# BBB_ADC7_inputs_with_mux_Ver1_Rev1.net
KiCad netlist of a schematic drawn in Altium Designer
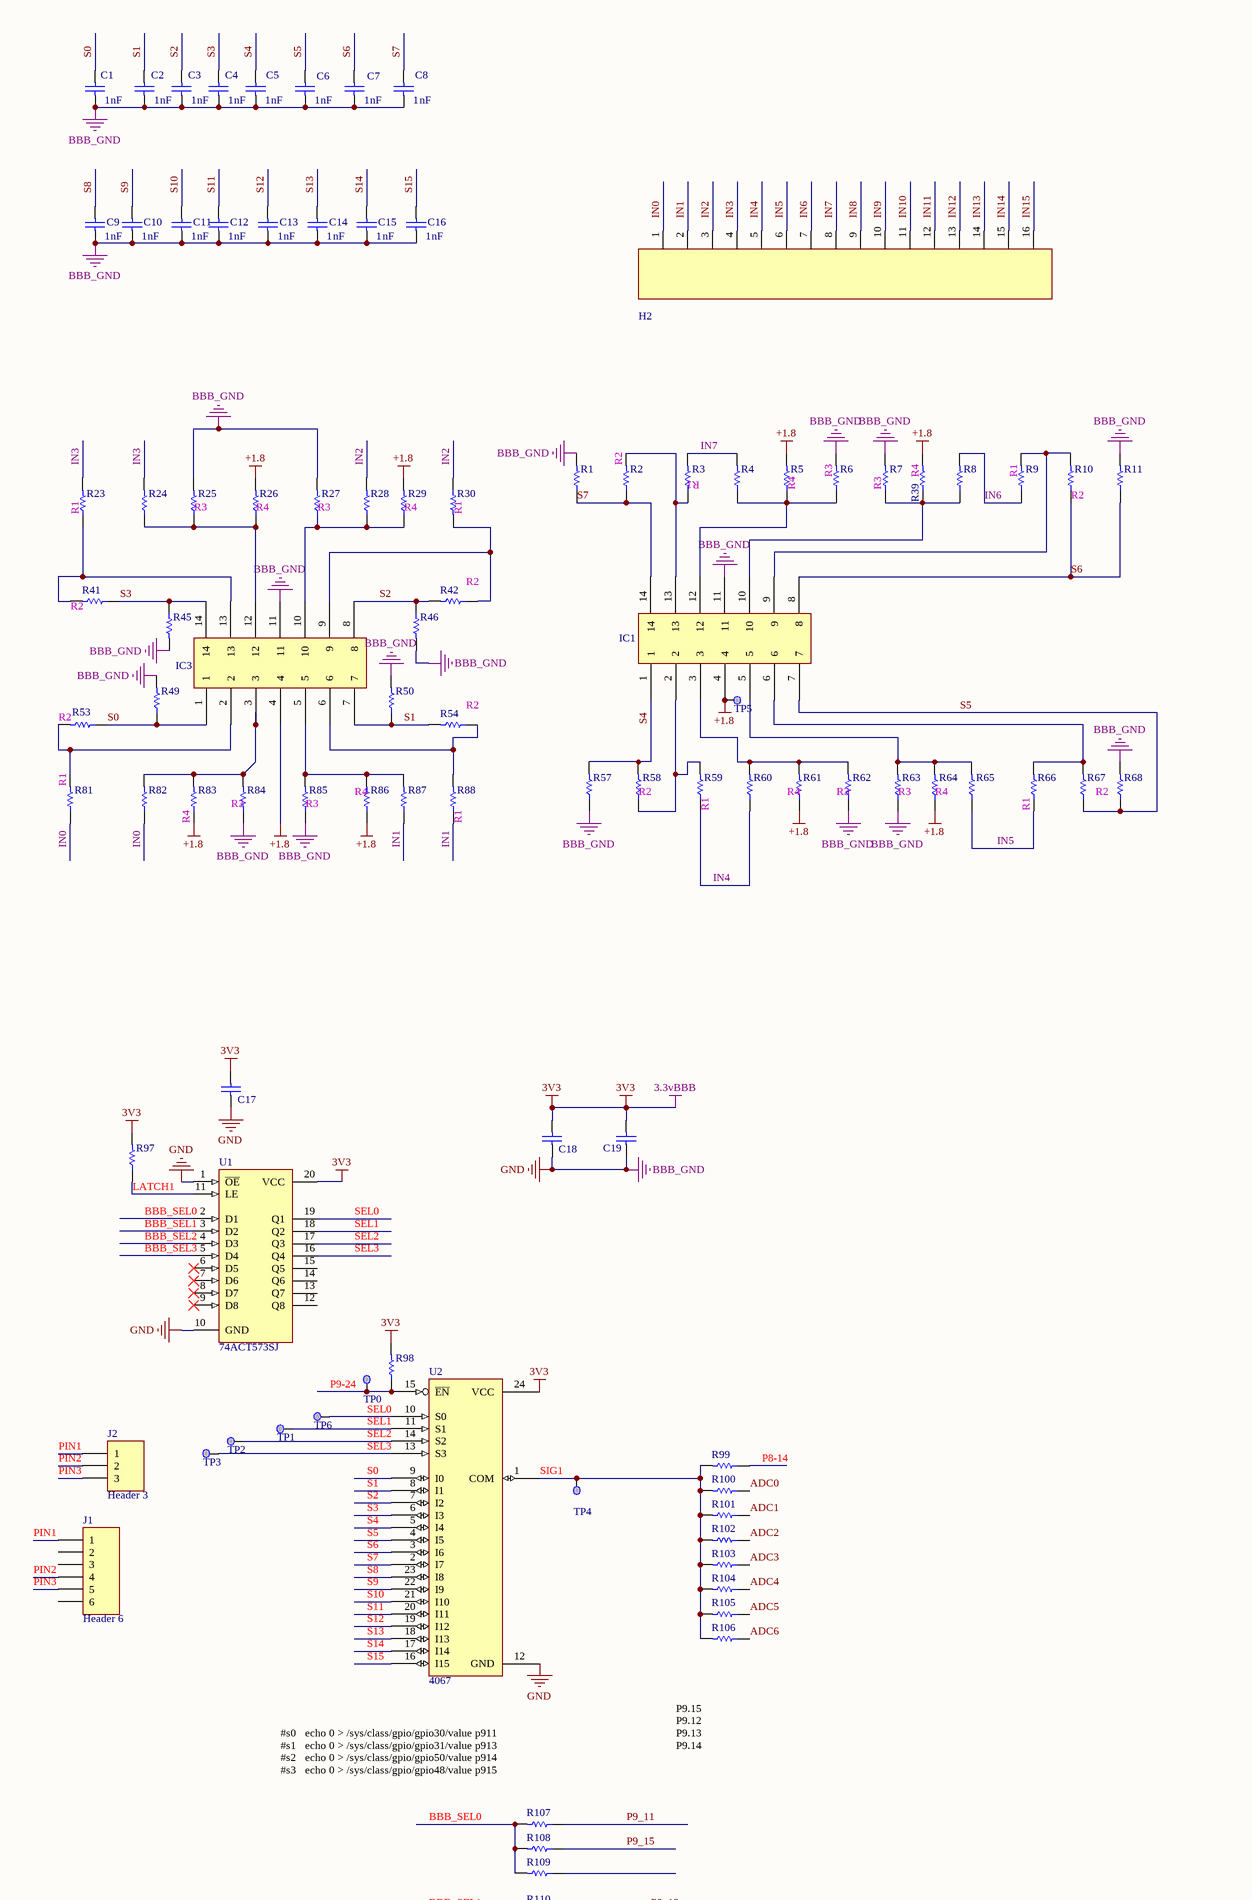
[diagram p0: BBB_ADC7_inputs_with_mux_Ver1 Rev1.SchDoc, top left]
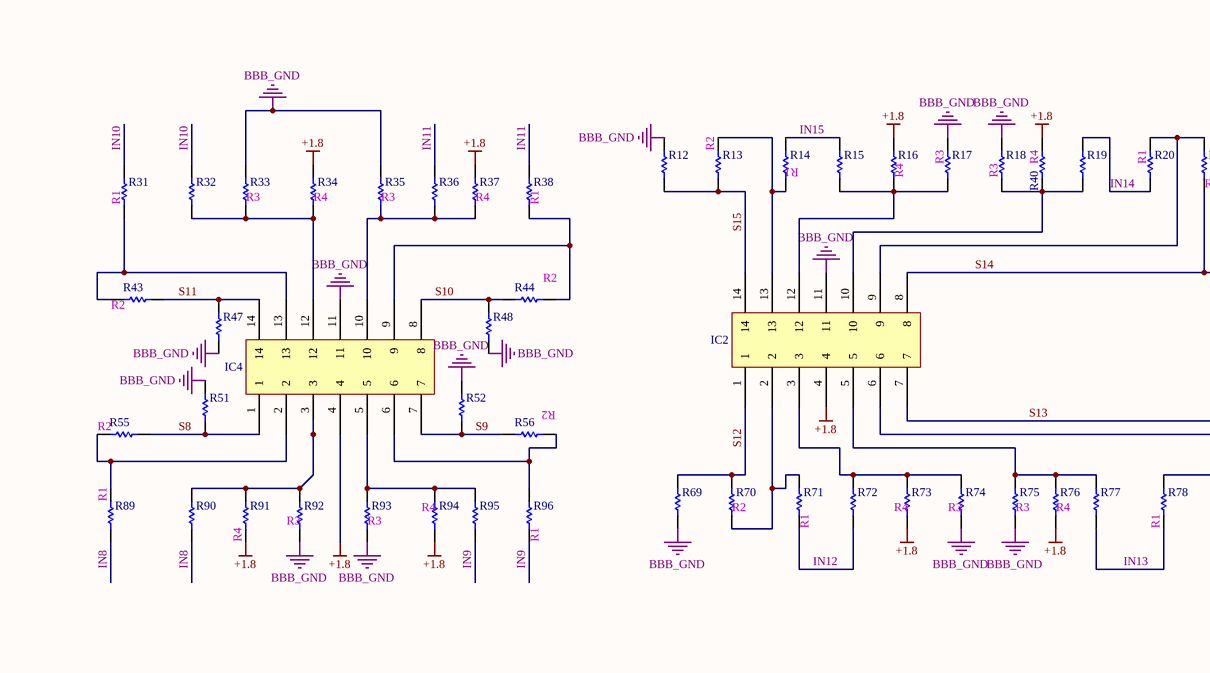
[diagram p1: BBB_ADC7_inputs_with_mux_Ver1 Rev1.SchDoc, top middle]
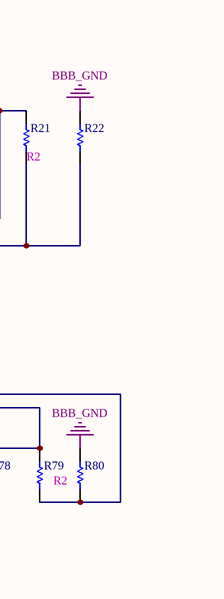
[diagram p2: BBB_ADC7_inputs_with_mux_Ver1 Rev1.SchDoc, top right]
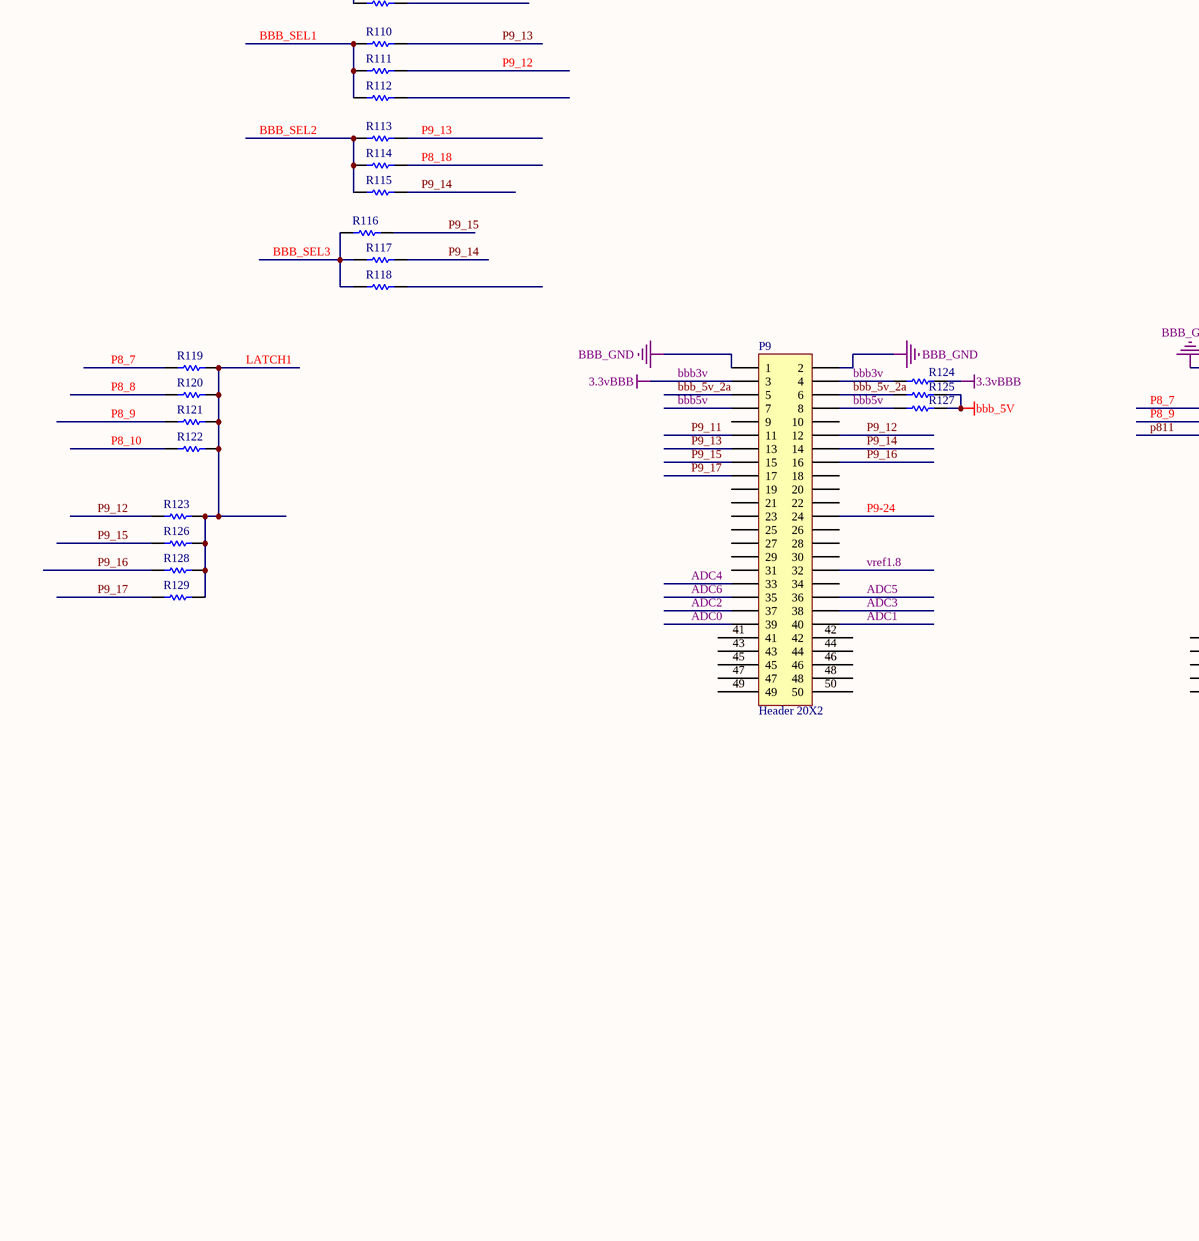
[diagram p3: BBB_ADC7_inputs_with_mux_Ver1 Rev1.SchDoc, bottom left]
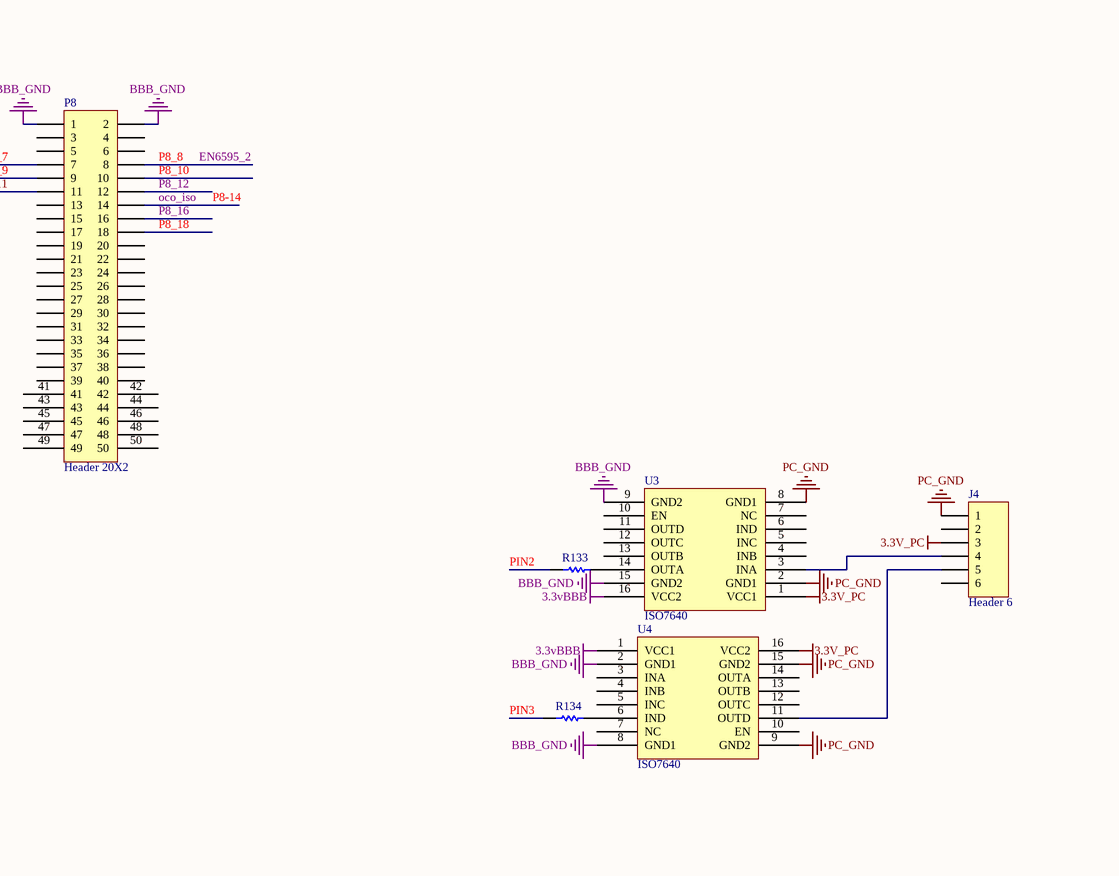
[diagram p4: BBB_ADC7_inputs_with_mux_Ver1 Rev1.SchDoc, bottom middle]
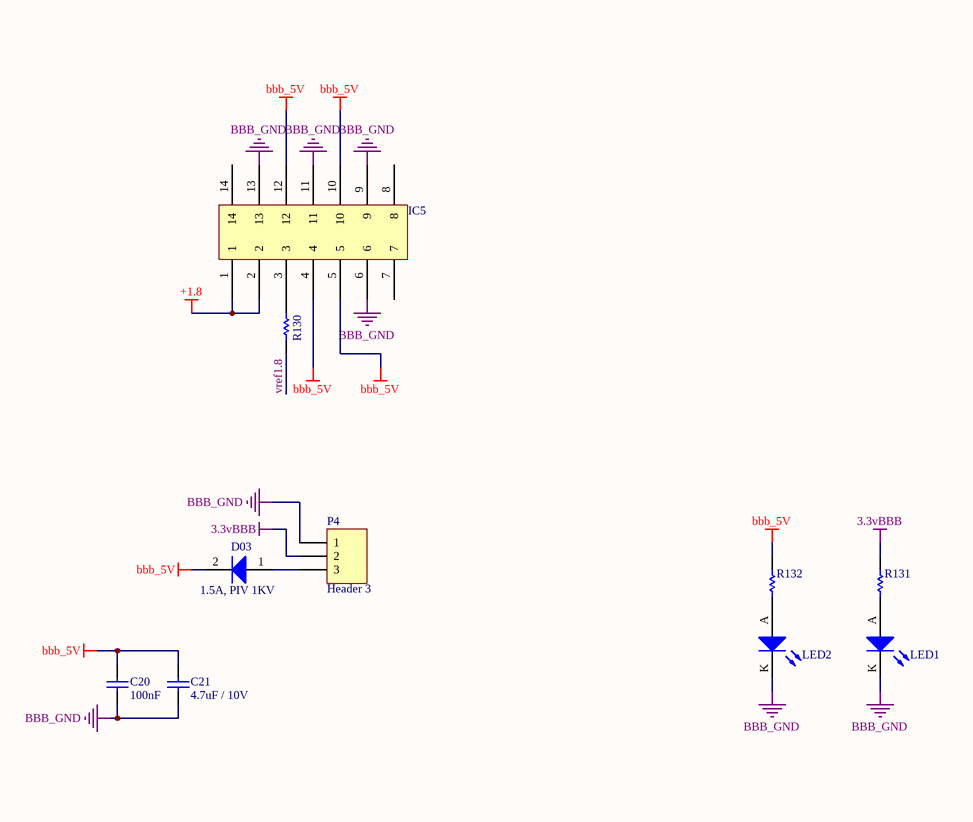
[diagram p5: BBB_ADC7_inputs_with_mux_Ver1 Rev1.SchDoc, bottom right]

(export (version "E")
  (design (tool "Eeschema 10.0.6"))
  (components
    (comp (ref "C1")
      (value "CAPACITOR NONPOLAR SMT")
      (footprint "C0402")
      (description "Capacitor ceramic, SMD 0402, 1 nF, +/-10%, 50 V dc")
      (fields
        (field (name "SMLPARTNO") "BCS22A-102")
        (field (name "UNITS OF CAPACITANCE") "nF")
        (field (name "CAPACITANCE") "1")
        (field (name "PUBLISHER") "Altium Limited")
      )
      (libsource (lib "Altium_DB-Lib_Agile9.3") (part "CAPACITOR NONPOLAR SMT"))
    )
    (comp (ref "C2")
      (value "CAPACITOR NONPOLAR SMT")
      (footprint "C0402")
      (description "Capacitor ceramic, SMD 0402, 1 nF, +/-10%, 50 V dc")
      (fields
        (field (name "SMLPARTNO") "BCS22A-102")
        (field (name "UNITS OF CAPACITANCE") "nF")
        (field (name "CAPACITANCE") "1")
        (field (name "PUBLISHER") "Altium Limited")
      )
      (libsource (lib "Altium_DB-Lib_Agile9.3") (part "CAPACITOR NONPOLAR SMT"))
    )
    (comp (ref "C3")
      (value "CAPACITOR NONPOLAR SMT")
      (footprint "C0402")
      (description "Capacitor ceramic, SMD 0402, 1 nF, +/-10%, 50 V dc")
      (fields
        (field (name "SMLPARTNO") "BCS22A-102")
        (field (name "UNITS OF CAPACITANCE") "nF")
        (field (name "CAPACITANCE") "1")
        (field (name "PUBLISHER") "Altium Limited")
      )
      (libsource (lib "Altium_DB-Lib_Agile9.3") (part "CAPACITOR NONPOLAR SMT"))
    )
    (comp (ref "C4")
      (value "CAPACITOR NONPOLAR SMT")
      (footprint "C0402")
      (description "Capacitor ceramic, SMD 0402, 1 nF, +/-10%, 50 V dc")
      (fields
        (field (name "SMLPARTNO") "BCS22A-102")
        (field (name "UNITS OF CAPACITANCE") "nF")
        (field (name "CAPACITANCE") "1")
        (field (name "PUBLISHER") "Altium Limited")
      )
      (libsource (lib "Altium_DB-Lib_Agile9.3") (part "CAPACITOR NONPOLAR SMT"))
    )
    (comp (ref "C5")
      (value "CAPACITOR NONPOLAR SMT")
      (footprint "C0402")
      (description "Capacitor ceramic, SMD 0402, 1 nF, +/-10%, 50 V dc")
      (fields
        (field (name "SMLPARTNO") "BCS22A-102")
        (field (name "UNITS OF CAPACITANCE") "nF")
        (field (name "CAPACITANCE") "1")
        (field (name "PUBLISHER") "Altium Limited")
      )
      (libsource (lib "Altium_DB-Lib_Agile9.3") (part "CAPACITOR NONPOLAR SMT"))
    )
    (comp (ref "C6")
      (value "CAPACITOR NONPOLAR SMT")
      (footprint "C0402")
      (description "Capacitor ceramic, SMD 0402, 1 nF, +/-10%, 50 V dc")
      (fields
        (field (name "SMLPARTNO") "BCS22A-102")
        (field (name "UNITS OF CAPACITANCE") "nF")
        (field (name "CAPACITANCE") "1")
        (field (name "PUBLISHER") "Altium Limited")
      )
      (libsource (lib "Altium_DB-Lib_Agile9.3") (part "CAPACITOR NONPOLAR SMT"))
    )
    (comp (ref "C7")
      (value "CAPACITOR NONPOLAR SMT")
      (footprint "C0402")
      (description "Capacitor ceramic, SMD 0402, 1 nF, +/-10%, 50 V dc")
      (fields
        (field (name "SMLPARTNO") "BCS22A-102")
        (field (name "UNITS OF CAPACITANCE") "nF")
        (field (name "CAPACITANCE") "1")
        (field (name "PUBLISHER") "Altium Limited")
      )
      (libsource (lib "Altium_DB-Lib_Agile9.3") (part "CAPACITOR NONPOLAR SMT"))
    )
    (comp (ref "C8")
      (value "CAPACITOR NONPOLAR SMT")
      (footprint "C0402")
      (description "Capacitor ceramic, SMD 0402, 1 nF, +/-10%, 50 V dc")
      (fields
        (field (name "SMLPARTNO") "BCS22A-102")
        (field (name "UNITS OF CAPACITANCE") "nF")
        (field (name "CAPACITANCE") "1")
        (field (name "PUBLISHER") "Altium Limited")
      )
      (libsource (lib "Altium_DB-Lib_Agile9.3") (part "CAPACITOR NONPOLAR SMT"))
    )
    (comp (ref "C9")
      (value "CAPACITOR NONPOLAR SMT")
      (footprint "C0402")
      (description "Capacitor ceramic, SMD 0402, 1 nF, +/-10%, 50 V dc")
      (fields
        (field (name "SMLPARTNO") "BCS22A-102")
        (field (name "UNITS OF CAPACITANCE") "nF")
        (field (name "CAPACITANCE") "1")
        (field (name "PUBLISHER") "Altium Limited")
      )
      (libsource (lib "Altium_DB-Lib_Agile9.3") (part "CAPACITOR NONPOLAR SMT"))
    )
    (comp (ref "C10")
      (value "CAPACITOR NONPOLAR SMT")
      (footprint "C0402")
      (description "Capacitor ceramic, SMD 0402, 1 nF, +/-10%, 50 V dc")
      (fields
        (field (name "SMLPARTNO") "BCS22A-102")
        (field (name "UNITS OF CAPACITANCE") "nF")
        (field (name "CAPACITANCE") "1")
        (field (name "PUBLISHER") "Altium Limited")
      )
      (libsource (lib "Altium_DB-Lib_Agile9.3") (part "CAPACITOR NONPOLAR SMT"))
    )
    (comp (ref "C11")
      (value "CAPACITOR NONPOLAR SMT")
      (footprint "C0402")
      (description "Capacitor ceramic, SMD 0402, 1 nF, +/-10%, 50 V dc")
      (fields
        (field (name "SMLPARTNO") "BCS22A-102")
        (field (name "UNITS OF CAPACITANCE") "nF")
        (field (name "CAPACITANCE") "1")
        (field (name "PUBLISHER") "Altium Limited")
      )
      (libsource (lib "Altium_DB-Lib_Agile9.3") (part "CAPACITOR NONPOLAR SMT"))
    )
    (comp (ref "C12")
      (value "CAPACITOR NONPOLAR SMT")
      (footprint "C0402")
      (description "Capacitor ceramic, SMD 0402, 1 nF, +/-10%, 50 V dc")
      (fields
        (field (name "SMLPARTNO") "BCS22A-102")
        (field (name "UNITS OF CAPACITANCE") "nF")
        (field (name "CAPACITANCE") "1")
        (field (name "PUBLISHER") "Altium Limited")
      )
      (libsource (lib "Altium_DB-Lib_Agile9.3") (part "CAPACITOR NONPOLAR SMT"))
    )
    (comp (ref "C13")
      (value "CAPACITOR NONPOLAR SMT")
      (footprint "C0402")
      (description "Capacitor ceramic, SMD 0402, 1 nF, +/-10%, 50 V dc")
      (fields
        (field (name "SMLPARTNO") "BCS22A-102")
        (field (name "UNITS OF CAPACITANCE") "nF")
        (field (name "CAPACITANCE") "1")
        (field (name "PUBLISHER") "Altium Limited")
      )
      (libsource (lib "Altium_DB-Lib_Agile9.3") (part "CAPACITOR NONPOLAR SMT"))
    )
    (comp (ref "C14")
      (value "CAPACITOR NONPOLAR SMT")
      (footprint "C0402")
      (description "Capacitor ceramic, SMD 0402, 1 nF, +/-10%, 50 V dc")
      (fields
        (field (name "SMLPARTNO") "BCS22A-102")
        (field (name "UNITS OF CAPACITANCE") "nF")
        (field (name "CAPACITANCE") "1")
        (field (name "PUBLISHER") "Altium Limited")
      )
      (libsource (lib "Altium_DB-Lib_Agile9.3") (part "CAPACITOR NONPOLAR SMT"))
    )
    (comp (ref "C15")
      (value "CAPACITOR NONPOLAR SMT")
      (footprint "C0402")
      (description "Capacitor ceramic, SMD 0402, 1 nF, +/-10%, 50 V dc")
      (fields
        (field (name "SMLPARTNO") "BCS22A-102")
        (field (name "UNITS OF CAPACITANCE") "nF")
        (field (name "CAPACITANCE") "1")
        (field (name "PUBLISHER") "Altium Limited")
      )
      (libsource (lib "Altium_DB-Lib_Agile9.3") (part "CAPACITOR NONPOLAR SMT"))
    )
    (comp (ref "C16")
      (value "CAPACITOR NONPOLAR SMT")
      (footprint "C0402")
      (description "Capacitor ceramic, SMD 0402, 1 nF, +/-10%, 50 V dc")
      (fields
        (field (name "SMLPARTNO") "BCS22A-102")
        (field (name "UNITS OF CAPACITANCE") "nF")
        (field (name "CAPACITANCE") "1")
        (field (name "PUBLISHER") "Altium Limited")
      )
      (libsource (lib "Altium_DB-Lib_Agile9.3") (part "CAPACITOR NONPOLAR SMT"))
    )
    (comp (ref "C17")
      (value "4.7uF, 10V")
      (footprint "C0603")
      (description "Capacitor ceramic, SMD 0603, 4.7 uF, +/-10%, 10 V dc")
      (fields (field (name "SMLPARTNO") "BCS129-475") (field (name "PUBLISHER") "Altium Limited"))
      (libsource (lib "Altium_DB-Lib_Agile9.3") (part "CAPACITOR NONPOLAR SMT"))
    )
    (comp (ref "C18")
      (value "4.7uF, 10V")
      (footprint "C0603")
      (description "Capacitor ceramic, SMD 0603, 4.7 uF, +/-10%, 10 V dc")
      (fields (field (name "SMLPARTNO") "BCS129-475") (field (name "PUBLISHER") "Altium Limited"))
      (libsource (lib "Altium_DB-Lib_Agile9.3") (part "CAPACITOR NONPOLAR SMT"))
    )
    (comp (ref "C19")
      (value "4.7uF, 10V")
      (footprint "C0603")
      (description "Capacitor ceramic, SMD 0603, 4.7 uF, +/-10%, 10 V dc")
      (fields (field (name "SMLPARTNO") "BCS129-475") (field (name "PUBLISHER") "Altium Limited"))
      (libsource (lib "Altium_DB-Lib_Agile9.3") (part "CAPACITOR NONPOLAR SMT"))
    )
    (comp (ref "C20")
      (value "100nF")
      (footprint "C0603")
      (description "Capacitor ceramic, SMD 0603, 100 nF, +/-10%, 16 V dc")
      (fields (field (name "SMLPARTNO") "BCS129-104") (field (name "PUBLISHER") "Altium Limited"))
      (libsource (lib "Altium_DB-Lib_Agile9.3") (part "CAPACITOR NONPOLAR SMT"))
    )
    (comp (ref "C21")
      (value "4.7uF / 10V")
      (footprint "C0603")
      (description "Capacitor ceramic, SMD 0603, 4.7 uF, +/-10%, 10 V dc")
      (fields (field (name "SMLPARTNO") "BCS129-475") (field (name "PUBLISHER") "Altium Limited"))
      (libsource (lib "Altium_DB-Lib_Agile9.3") (part "CAPACITOR NONPOLAR SMT"))
    )
    (comp (ref "D03")
      (value "1.5A, PIV 1KV")
      (footprint "DIODE_DO-214AA(SMB)")
      (description "Diode high voltage, SMD DO-214AA, If 1.5 A, PIV 1 kV")
      (fields (field (name "SMLPARTNO") "BDS334-001") (field (name "PUBLISHER") "Altium Limited"))
      (libsource (lib "Altium_DB-Lib_Agile9.3") (part "DIODE"))
    )
    (comp (ref "H2")
      (value "connector 16 pin male_ stright")
      (footprint "16 pin male stright")
      (libsource (lib "PPE_integrated_LIB") (part "connector 16 pin male_ stright"))
    )
    (comp (ref "IC1")
      (value "OPamp")
      (footprint "SOIC-14")
      (fields (field (name "SMLPARTNO") "BIS114-020"))
      (libsource (lib "Schlib2") (part "OPamp"))
    )
    (comp (ref "IC2")
      (value "OPamp")
      (footprint "SOIC-14")
      (fields (field (name "SMLPARTNO") "BIS114-020"))
      (libsource (lib "Schlib2") (part "OPamp"))
    )
    (comp (ref "IC3")
      (value "OPamp")
      (footprint "SOIC-14")
      (fields (field (name "SMLPARTNO") "BIS114-020"))
      (libsource (lib "Schlib2") (part "OPamp"))
    )
    (comp (ref "IC4")
      (value "OPamp")
      (footprint "SOIC-14")
      (fields (field (name "SMLPARTNO") "BIS114-020"))
      (libsource (lib "Schlib2") (part "OPamp"))
    )
    (comp (ref "IC5")
      (value "OPamp")
      (footprint "SOIC-14")
      (fields (field (name "SMLPPARTNO") "BIS114-020"))
      (libsource (lib "Schlib2") (part "OPamp"))
    )
    (comp (ref "J1")
      (value "Header 6")
      (footprint "HDR1X6")
      (description "Header, 6-Pin")
      (fields (field (name "PUBLISHER") "Altium Limited"))
      (libsource (lib "Miscellaneous Connectors") (part "Header 6"))
    )
    (comp (ref "J2")
      (value "Header 3")
      (footprint "HDR1X3")
      (description "Header, 3-Pin")
      (fields (field (name "PUBLISHER") "Altium Limited"))
      (libsource (lib "Miscellaneous Connectors") (part "Header 3"))
    )
    (comp (ref "J4")
      (value "Header 6")
      (footprint "HDR1X6")
      (description "Header, 6-Pin")
      (fields (field (name "PUBLISHER") "Altium Limited"))
      (libsource (lib "Miscellaneous Connectors") (part "Header 6"))
    )
    (comp (ref "LED1")
      (value "LED")
      (footprint "0537, LED, 1206")
      (description "Optoelectronic LED, SMD 1206, red colour")
      (fields (field (name "SMLPARTNO") "BDS461-001") (field (name "PUBLISHER") "Altium Limited"))
      (libsource (lib "Altium_DB-Lib_Agile9.3") (part "LED"))
    )
    (comp (ref "LED2")
      (value "LED")
      (footprint "0537, LED, 1206")
      (description "Optoelectronic LED, SMD 1206, red colour")
      (fields (field (name "SMLPARTNO") "BDS461-001") (field (name "PUBLISHER") "Altium Limited"))
      (libsource (lib "Altium_DB-Lib_Agile9.3") (part "LED"))
    )
    (comp (ref "P4")
      (value "Header 3")
      (footprint "HDR1X3")
      (description "Header, 3-Pin")
      (fields (field (name "PUBLISHER") "Altium Limited"))
      (libsource (lib "BBB ADS1247") (part "Header 3"))
    )
    (comp (ref "P8")
      (value "Header 20X2")
      (footprint "BBBHEADERNOHOLE")
      (description "Header, 20-Pin, Dual row")
      (fields (field (name "PUBLISHER") "Altium Limited"))
      (libsource (lib "PantherTester") (part "Header 20X2"))
    )
    (comp (ref "P9")
      (value "Header 20X2")
      (footprint "BBBHEADERNOHOLE")
      (description "Header, 20-Pin, Dual row")
      (fields (field (name "PUBLISHER") "Altium Limited"))
      (libsource (lib "PantherTester") (part "Header 20X2"))
    )
    (comp (ref "R1")
      (value "Resistor SMD 0603, 100 k Ohm, +/-5%, 1/10W")
      (footprint "0603")
      (fields (field (name "SMLPARTNO") "BRS131-104") (field (name "TOLERANCE") "+/-5%"))
      (libsource (lib "Altium_DB-Lib_Agile9.3") (part "RESISTOR SMT"))
    )
    (comp (ref "R2")
      (value "Resistor SMD 0603, 1.5 k Ohm, +/-5%, 1/10W")
      (footprint "0603")
      (fields (field (name "SMLPARTNO") "BRS131-152") (field (name "TOLERANCE") "+/-5%"))
      (libsource (lib "Altium_DB-Lib_Agile9.3") (part "RESISTOR SMT"))
    )
    (comp (ref "R3")
      (value "Resistor SMD 0603, 9.1 k Ohm, +/-5%, 1/10W")
      (footprint "0603")
      (fields (field (name "SMLPARTNO") "BRS131-912") (field (name "TOLERANCE") "+/-5%"))
      (libsource (lib "Altium_DB-Lib_Agile9.3") (part "RESISTOR SMT"))
    )
    (comp (ref "R4")
      (value "open")
      (footprint "0603")
      (fields (field (name "TOLERANCE") "+/-5%"))
      (libsource (lib "Altium_DB-Lib_Agile9.3") (part "RESISTOR SMT"))
    )
    (comp (ref "R5")
      (value "Resistor SMD 0603, 6.8 k Ohm, +/-1%, 1/10W")
      (footprint "0603")
      (fields (field (name "SMLPARTNO") "BRS131-682") (field (name "TOLERANCE") "+/-5%"))
      (libsource (lib "Altium_DB-Lib_Agile9.3") (part "RESISTOR SMT"))
    )
    (comp (ref "R6")
      (value "Resistor SMD 0603, 4.7 k Ohm, +/-5%, 1/10W")
      (footprint "0603")
      (fields (field (name "SMLPARTNO") "BRS133-472") (field (name "TOLERANCE") "+/-5%"))
      (libsource (lib "Altium_DB-Lib_Agile9.3") (part "RESISTOR SMT"))
    )
    (comp (ref "R7")
      (value "Resistor SMD 0603, 4.7 k Ohm, +/-5%, 1/10W")
      (footprint "0603")
      (fields (field (name "SMLPARTNO") "BRS133-472") (field (name "TOLERANCE") "+/-5%"))
      (libsource (lib "Altium_DB-Lib_Agile9.3") (part "RESISTOR SMT"))
    )
    (comp (ref "R8")
      (value "open")
      (footprint "0603")
      (fields (field (name "TOLERANCE") "+/-5%"))
      (libsource (lib "Altium_DB-Lib_Agile9.3") (part "RESISTOR SMT"))
    )
    (comp (ref "R9")
      (value "Resistor SMD 0603, 9.1 k Ohm, +/-5%, 1/10W")
      (footprint "0603")
      (fields (field (name "SMLPARTNO") "BRS131-912") (field (name "TOLERANCE") "+/-5%"))
      (libsource (lib "Altium_DB-Lib_Agile9.3") (part "RESISTOR SMT"))
    )
    (comp (ref "R10")
      (value "Resistor SMD 0603, 1.5 k Ohm, +/-5%, 1/10W")
      (footprint "0603")
      (fields (field (name "SMLPARTNO") "BRS131-152") (field (name "TOLERANCE") "+/-5%"))
      (libsource (lib "Altium_DB-Lib_Agile9.3") (part "RESISTOR SMT"))
    )
    (comp (ref "R11")
      (value "Resistor SMD 0603, 100 k Ohm, +/-5%, 1/10W")
      (footprint "0603")
      (fields (field (name "SMLPARTNO") "BRS131-104") (field (name "TOLERANCE") "+/-5%"))
      (libsource (lib "Altium_DB-Lib_Agile9.3") (part "RESISTOR SMT"))
    )
    (comp (ref "R12")
      (value "Resistor SMD 0603, 100 k Ohm, +/-5%, 1/10W")
      (footprint "0603")
      (fields (field (name "SMLPARTNO") "BRS131-104") (field (name "TOLERANCE") "+/-5%"))
      (libsource (lib "Altium_DB-Lib_Agile9.3") (part "RESISTOR SMT"))
    )
    (comp (ref "R13")
      (value "Resistor SMD 0603, 1.5 k Ohm, +/-5%, 1/10W")
      (footprint "0603")
      (fields (field (name "SMLPARTNO") "BRS131-152") (field (name "TOLERANCE") "+/-5%"))
      (libsource (lib "Altium_DB-Lib_Agile9.3") (part "RESISTOR SMT"))
    )
    (comp (ref "R14")
      (value "Resistor SMD 0603, 9.1 k Ohm, +/-5%, 1/10W")
      (footprint "0603")
      (fields (field (name "SMLPARTNO") "BRS131-912") (field (name "TOLERANCE") "+/-5%"))
      (libsource (lib "Altium_DB-Lib_Agile9.3") (part "RESISTOR SMT"))
    )
    (comp (ref "R15")
      (value "open")
      (footprint "0603")
      (fields (field (name "TOLERANCE") "+/-5%"))
      (libsource (lib "Altium_DB-Lib_Agile9.3") (part "RESISTOR SMT"))
    )
    (comp (ref "R16")
      (value "Resistor SMD 0603, 6.8 k Ohm, +/-1%, 1/10W")
      (footprint "0603")
      (fields (field (name "SMLPARTNO") "BRS131-682") (field (name "TOLERANCE") "+/-5%"))
      (libsource (lib "Altium_DB-Lib_Agile9.3") (part "RESISTOR SMT"))
    )
    (comp (ref "R17")
      (value "Resistor SMD 0603, 4.7 k Ohm, +/-5%, 1/10W")
      (footprint "0603")
      (fields (field (name "SMLPARTNO") "BRS133-472") (field (name "TOLERANCE") "+/-5%"))
      (libsource (lib "Altium_DB-Lib_Agile9.3") (part "RESISTOR SMT"))
    )
    (comp (ref "R18")
      (value "Resistor SMD 0603, 4.7 k Ohm, +/-5%, 1/10W")
      (footprint "0603")
      (fields (field (name "SMLPARTNO") "BRS133-472") (field (name "TOLERANCE") "+/-5%"))
      (libsource (lib "Altium_DB-Lib_Agile9.3") (part "RESISTOR SMT"))
    )
    (comp (ref "R19")
      (value "open")
      (footprint "0603")
      (fields (field (name "TOLERANCE") "+/-5%"))
      (libsource (lib "Altium_DB-Lib_Agile9.3") (part "RESISTOR SMT"))
    )
    (comp (ref "R20")
      (value "Resistor SMD 0603, 9.1 k Ohm, +/-5%, 1/10W")
      (footprint "0603")
      (fields (field (name "SMLPARTNO") "BRS131-912") (field (name "TOLERANCE") "+/-5%"))
      (libsource (lib "Altium_DB-Lib_Agile9.3") (part "RESISTOR SMT"))
    )
    (comp (ref "R21")
      (value "Resistor SMD 0603, 1.5 k Ohm, +/-5%, 1/10W")
      (footprint "0603")
      (fields (field (name "SMLPARTNO") "BRS131-152") (field (name "TOLERANCE") "+/-5%"))
      (libsource (lib "Altium_DB-Lib_Agile9.3") (part "RESISTOR SMT"))
    )
    (comp (ref "R22")
      (value "Resistor SMD 0603, 100 k Ohm, +/-5%, 1/10W")
      (footprint "0603")
      (fields (field (name "SMLPARTNO") "BRS131-104") (field (name "TOLERANCE") "+/-5%"))
      (libsource (lib "Altium_DB-Lib_Agile9.3") (part "RESISTOR SMT"))
    )
    (comp (ref "R23")
      (value "Resistor SMD 0603, 9.1 k Ohm, +/-5%, 1/10W")
      (footprint "0603")
      (fields (field (name "SMLPARTNO") "BRS131-912") (field (name "TOLERANCE") "+/-5%"))
      (libsource (lib "Altium_DB-Lib_Agile9.3") (part "RESISTOR SMT"))
    )
    (comp (ref "R24")
      (value "OPEN")
      (footprint "0603")
      (fields (field (name "TOLERANCE") "+/-5%"))
      (libsource (lib "Altium_DB-Lib_Agile9.3") (part "RESISTOR SMT"))
    )
    (comp (ref "R25")
      (value "Resistor SMD 0603, 4.7 k Ohm, +/-5%, 1/10W")
      (footprint "0603")
      (fields (field (name "SMLPARTNO") "BRS133-472") (field (name "TOLERANCE") "+/-5%"))
      (libsource (lib "Altium_DB-Lib_Agile9.3") (part "RESISTOR SMT"))
    )
    (comp (ref "R26")
      (value "Resistor SMD 0603, 6.8 k Ohm, +/-1%, 1/10W")
      (footprint "0603")
      (fields (field (name "SMLPARTNO") "BRS131-682") (field (name "TOLERANCE") "+/-5%"))
      (libsource (lib "Altium_DB-Lib_Agile9.3") (part "RESISTOR SMT"))
    )
    (comp (ref "R27")
      (value "Resistor SMD 0603, 4.7 k Ohm, +/-5%, 1/10W")
      (footprint "0603")
      (fields (field (name "SMLPARTNO") "BRS133-472") (field (name "TOLERANCE") "+/-5%"))
      (libsource (lib "Altium_DB-Lib_Agile9.3") (part "RESISTOR SMT"))
    )
    (comp (ref "R28")
      (value "OPEN")
      (footprint "0603")
      (fields (field (name "TOLERANCE") "+/-5%"))
      (libsource (lib "Altium_DB-Lib_Agile9.3") (part "RESISTOR SMT"))
    )
    (comp (ref "R29")
      (value "Resistor SMD 0603, 6.8 k Ohm, +/-1%, 1/10W")
      (footprint "0603")
      (fields (field (name "SMLPARTNO") "BRS131-682") (field (name "TOLERANCE") "+/-5%"))
      (libsource (lib "Altium_DB-Lib_Agile9.3") (part "RESISTOR SMT"))
    )
    (comp (ref "R30")
      (value "Resistor SMD 0603, 9.1 k Ohm, +/-5%, 1/10W")
      (footprint "0603")
      (fields (field (name "SMLPARTNO") "BRS131-912") (field (name "TOLERANCE") "+/-5%"))
      (libsource (lib "Altium_DB-Lib_Agile9.3") (part "RESISTOR SMT"))
    )
    (comp (ref "R31")
      (value "Resistor SMD 0603, 9.1 k Ohm, +/-5%, 1/10W")
      (footprint "0603")
      (fields (field (name "SMLPARTNO") "BRS131-912") (field (name "TOLERANCE") "+/-5%"))
      (libsource (lib "Altium_DB-Lib_Agile9.3") (part "RESISTOR SMT"))
    )
    (comp (ref "R32")
      (value "OPEN")
      (footprint "0603")
      (fields (field (name "TOLERANCE") "+/-5%"))
      (libsource (lib "Altium_DB-Lib_Agile9.3") (part "RESISTOR SMT"))
    )
    (comp (ref "R33")
      (value "Resistor SMD 0603, 4.7 k Ohm, +/-5%, 1/10W")
      (footprint "0603")
      (fields (field (name "SMLPARTNO") "BRS133-472") (field (name "TOLERANCE") "+/-5%"))
      (libsource (lib "Altium_DB-Lib_Agile9.3") (part "RESISTOR SMT"))
    )
    (comp (ref "R34")
      (value "Resistor SMD 0603, 6.8 k Ohm, +/-1%, 1/10W")
      (footprint "0603")
      (fields (field (name "SMLPARTNO") "BRS131-682") (field (name "TOLERANCE") "+/-5%"))
      (libsource (lib "Altium_DB-Lib_Agile9.3") (part "RESISTOR SMT"))
    )
    (comp (ref "R35")
      (value "Resistor SMD 0603, 4.7 k Ohm, +/-5%, 1/10W")
      (footprint "0603")
      (fields (field (name "SMLPARTNO") "BRS133-472") (field (name "TOLERANCE") "+/-5%"))
      (libsource (lib "Altium_DB-Lib_Agile9.3") (part "RESISTOR SMT"))
    )
    (comp (ref "R36")
      (value "OPEN")
      (footprint "0603")
      (fields (field (name "TOLERANCE") "+/-5%"))
      (libsource (lib "Altium_DB-Lib_Agile9.3") (part "RESISTOR SMT"))
    )
    (comp (ref "R37")
      (value "Resistor SMD 0603, 6.8 k Ohm, +/-1%, 1/10W")
      (footprint "0603")
      (fields (field (name "SMLPARTNO") "BRS131-682") (field (name "TOLERANCE") "+/-5%"))
      (libsource (lib "Altium_DB-Lib_Agile9.3") (part "RESISTOR SMT"))
    )
    (comp (ref "R38")
      (value "Resistor SMD 0603, 9.1 k Ohm, +/-5%, 1/10W")
      (footprint "0603")
      (fields (field (name "SMLPARTNO") "BRS131-912") (field (name "TOLERANCE") "+/-5%"))
      (libsource (lib "Altium_DB-Lib_Agile9.3") (part "RESISTOR SMT"))
    )
    (comp (ref "R39")
      (value "Resistor SMD 0603, 6.8 k Ohm, +/-1%, 1/10W")
      (footprint "0603")
      (fields (field (name "SMLPARTNO") "BRS131-682") (field (name "TOLERANCE") "+/-5%"))
      (libsource (lib "Altium_DB-Lib_Agile9.3") (part "RESISTOR SMT"))
    )
    (comp (ref "R40")
      (value "Resistor SMD 0603, 6.8 k Ohm, +/-1%, 1/10W")
      (footprint "0603")
      (fields (field (name "SMLPARTNO") "BRS131-682") (field (name "TOLERANCE") "+/-5%"))
      (libsource (lib "Altium_DB-Lib_Agile9.3") (part "RESISTOR SMT"))
    )
    (comp (ref "R41")
      (value "Resistor SMD 0603, 1.5 k Ohm, +/-5%, 1/10W")
      (footprint "0603")
      (fields (field (name "SMLPARTNO") "BRS131-152") (field (name "TOLERANCE") "+/-5%"))
      (libsource (lib "Altium_DB-Lib_Agile9.3") (part "RESISTOR SMT"))
    )
    (comp (ref "R42")
      (value "Resistor SMD 0603, 1.5 k Ohm, +/-5%, 1/10W")
      (footprint "0603")
      (fields (field (name "SMLPARTNO") "BRS131-152") (field (name "TOLERANCE") "+/-5%"))
      (libsource (lib "Altium_DB-Lib_Agile9.3") (part "RESISTOR SMT"))
    )
    (comp (ref "R43")
      (value "Resistor SMD 0603, 1.5 k Ohm, +/-5%, 1/10W")
      (footprint "0603")
      (fields (field (name "SMLPARTNO") "BRS131-152") (field (name "TOLERANCE") "+/-5%"))
      (libsource (lib "Altium_DB-Lib_Agile9.3") (part "RESISTOR SMT"))
    )
    (comp (ref "R44")
      (value "Resistor SMD 0603, 1.5 k Ohm, +/-5%, 1/10W")
      (footprint "0603")
      (fields (field (name "SMLPARTNO") "BRS131-152") (field (name "TOLERANCE") "+/-5%"))
      (libsource (lib "Altium_DB-Lib_Agile9.3") (part "RESISTOR SMT"))
    )
    (comp (ref "R45")
      (value "Resistor SMD 0603, 100 k Ohm, +/-5%, 1/10W")
      (footprint "0603")
      (fields (field (name "SMLPARTNO") "BRS131-104") (field (name "TOLERANCE") "+/-5%"))
      (libsource (lib "Altium_DB-Lib_Agile9.3") (part "RESISTOR SMT"))
    )
    (comp (ref "R46")
      (value "Resistor SMD 0603, 100 k Ohm, +/-5%, 1/10W")
      (footprint "0603")
      (fields (field (name "SMLPARTNO") "BRS131-104") (field (name "TOLERANCE") "+/-5%"))
      (libsource (lib "Altium_DB-Lib_Agile9.3") (part "RESISTOR SMT"))
    )
    (comp (ref "R47")
      (value "Resistor SMD 0603, 100 k Ohm, +/-5%, 1/10W")
      (footprint "0603")
      (fields (field (name "SMLPARTNO") "BRS131-104") (field (name "TOLERANCE") "+/-5%"))
      (libsource (lib "Altium_DB-Lib_Agile9.3") (part "RESISTOR SMT"))
    )
    (comp (ref "R48")
      (value "Resistor SMD 0603, 100 k Ohm, +/-5%, 1/10W")
      (footprint "0603")
      (fields (field (name "SMLPARTNO") "BRS131-104") (field (name "TOLERANCE") "+/-5%"))
      (libsource (lib "Altium_DB-Lib_Agile9.3") (part "RESISTOR SMT"))
    )
    (comp (ref "R49")
      (value "Resistor SMD 0603, 100 k Ohm, +/-5%, 1/10W")
      (footprint "0603")
      (fields (field (name "SMLPARTNO") "BRS131-104") (field (name "TOLERANCE") "+/-5%"))
      (libsource (lib "Altium_DB-Lib_Agile9.3") (part "RESISTOR SMT"))
    )
    (comp (ref "R50")
      (value "Resistor SMD 0603, 100 k Ohm, +/-5%, 1/10W")
      (footprint "0603")
      (fields (field (name "SMLPARTNO") "BRS131-104") (field (name "TOLERANCE") "+/-5%"))
      (libsource (lib "Altium_DB-Lib_Agile9.3") (part "RESISTOR SMT"))
    )
    (comp (ref "R51")
      (value "Resistor SMD 0603, 100 k Ohm, +/-5%, 1/10W")
      (footprint "0603")
      (fields (field (name "SMLPARTNO") "BRS131-104") (field (name "TOLERANCE") "+/-5%"))
      (libsource (lib "Altium_DB-Lib_Agile9.3") (part "RESISTOR SMT"))
    )
    (comp (ref "R52")
      (value "Resistor SMD 0603, 100 k Ohm, +/-5%, 1/10W")
      (footprint "0603")
      (fields (field (name "SMLPARTNO") "BRS131-104") (field (name "TOLERANCE") "+/-5%"))
      (libsource (lib "Altium_DB-Lib_Agile9.3") (part "RESISTOR SMT"))
    )
    (comp (ref "R53")
      (value "Resistor SMD 0603, 1.5 k Ohm, +/-5%, 1/10W")
      (footprint "0603")
      (fields (field (name "SMLPARTNO") "BRS131-152") (field (name "TOLERANCE") "+/-5%"))
      (libsource (lib "Altium_DB-Lib_Agile9.3") (part "RESISTOR SMT"))
    )
    (comp (ref "R54")
      (value "Resistor SMD 0603, 1.5 k Ohm, +/-5%, 1/10W")
      (footprint "0603")
      (fields (field (name "SMLPARTNO") "BRS131-152") (field (name "TOLERANCE") "+/-5%"))
      (libsource (lib "Altium_DB-Lib_Agile9.3") (part "RESISTOR SMT"))
    )
    (comp (ref "R55")
      (value "Resistor SMD 0603, 1.5 k Ohm, +/-5%, 1/10W")
      (footprint "0603")
      (fields (field (name "SMLPARTNO") "BRS131-152") (field (name "TOLERANCE") "+/-5%"))
      (libsource (lib "Altium_DB-Lib_Agile9.3") (part "RESISTOR SMT"))
    )
    (comp (ref "R56")
      (value "Resistor SMD 0603, 1.5 k Ohm, +/-5%, 1/10W")
      (footprint "0603")
      (fields (field (name "SMLPARTNO") "BRS131-152") (field (name "TOLERANCE") "+/-5%"))
      (libsource (lib "Altium_DB-Lib_Agile9.3") (part "RESISTOR SMT"))
    )
    (comp (ref "R57")
      (value "Resistor SMD 0603, 100 k Ohm, +/-5%, 1/10W")
      (footprint "0603")
      (fields (field (name "SMLPARTNO") "BRS131-104") (field (name "TOLERANCE") "+/-5%"))
      (libsource (lib "Altium_DB-Lib_Agile9.3") (part "RESISTOR SMT"))
    )
    (comp (ref "R58")
      (value "Resistor SMD 0603, 1.5 k Ohm, +/-5%, 1/10W")
      (footprint "0603")
      (fields (field (name "SMLPARTNO") "BRS131-152") (field (name "TOLERANCE") "+/-5%"))
      (libsource (lib "Altium_DB-Lib_Agile9.3") (part "RESISTOR SMT"))
    )
    (comp (ref "R59")
      (value "Resistor SMD 0603, 9.1 k Ohm, +/-5%, 1/10W")
      (footprint "0603")
      (fields (field (name "SMLPARTNO") "BRS133-902") (field (name "TOLERANCE") "+/-5%"))
      (libsource (lib "Altium_DB-Lib_Agile9.3") (part "RESISTOR SMT"))
    )
    (comp (ref "R60")
      (value "open")
      (footprint "0603")
      (fields (field (name "TOLERANCE") "+/-5%"))
      (libsource (lib "Altium_DB-Lib_Agile9.3") (part "RESISTOR SMT"))
    )
    (comp (ref "R61")
      (value "Resistor SMD 0603, 6.8 k Ohm, +/-1%, 1/10W")
      (footprint "0603")
      (fields (field (name "SMLPARTNO") "BRS131-682") (field (name "TOLERANCE") "+/-5%"))
      (libsource (lib "Altium_DB-Lib_Agile9.3") (part "RESISTOR SMT"))
    )
    (comp (ref "R62")
      (value "Resistor SMD 0603, 4.7 k Ohm, +/-5%, 1/10W")
      (footprint "0603")
      (fields (field (name "SMLPARTNO") "BRS133-472") (field (name "TOLERANCE") "+/-5%"))
      (libsource (lib "Altium_DB-Lib_Agile9.3") (part "RESISTOR SMT"))
    )
    (comp (ref "R63")
      (value "Resistor SMD 0603, 4.7 k Ohm, +/-5%, 1/10W")
      (footprint "0603")
      (fields (field (name "SMLPARTNO") "BRS133-472") (field (name "TOLERANCE") "+/-5%"))
      (libsource (lib "Altium_DB-Lib_Agile9.3") (part "RESISTOR SMT"))
    )
    (comp (ref "R64")
      (value "Resistor SMD 0603, 6.8 k Ohm, +/-1%, 1/10W")
      (footprint "0603")
      (fields (field (name "SMLPARTNO") "BRS131-682") (field (name "TOLERANCE") "+/-5%"))
      (libsource (lib "Altium_DB-Lib_Agile9.3") (part "RESISTOR SMT"))
    )
    (comp (ref "R65")
      (value "open")
      (footprint "0603")
      (fields (field (name "TOLERANCE") "+/-5%"))
      (libsource (lib "Altium_DB-Lib_Agile9.3") (part "RESISTOR SMT"))
    )
    (comp (ref "R66")
      (value "Resistor SMD 0603, 9.1 k Ohm, +/-5%, 1/10W")
      (footprint "0603")
      (fields (field (name "SMLPARTNO") "BRS131-912") (field (name "TOLERANCE") "+/-5%"))
      (libsource (lib "Altium_DB-Lib_Agile9.3") (part "RESISTOR SMT"))
    )
    (comp (ref "R67")
      (value "Resistor SMD 0603, 1.5 k Ohm, +/-5%, 1/10W")
      (footprint "0603")
      (fields (field (name "SMLPARTNO") "BRS131-152") (field (name "TOLERANCE") "+/-5%"))
      (libsource (lib "Altium_DB-Lib_Agile9.3") (part "RESISTOR SMT"))
    )
    (comp (ref "R68")
      (value "Resistor SMD 0603, 100 k Ohm, +/-5%, 1/10W")
      (footprint "0603")
      (fields (field (name "SMLPARTNO") "BRS131-104") (field (name "TOLERANCE") "+/-5%"))
      (libsource (lib "Altium_DB-Lib_Agile9.3") (part "RESISTOR SMT"))
    )
    (comp (ref "R69")
      (value "Resistor SMD 0603, 100 k Ohm, +/-5%, 1/10W")
      (footprint "0603")
      (fields (field (name "SMLPARTNO") "BRS131-104") (field (name "TOLERANCE") "+/-5%"))
      (libsource (lib "Altium_DB-Lib_Agile9.3") (part "RESISTOR SMT"))
    )
    (comp (ref "R70")
      (value "Resistor SMD 0603, 1.5 k Ohm, +/-5%, 1/10W")
      (footprint "0603")
      (fields (field (name "SMLPARTNO") "BRS131-152") (field (name "TOLERANCE") "+/-5%"))
      (libsource (lib "Altium_DB-Lib_Agile9.3") (part "RESISTOR SMT"))
    )
    (comp (ref "R71")
      (value "Resistor SMD 0603, 9.1 k Ohm, +/-5%, 1/10W")
      (footprint "0603")
      (fields (field (name "SMLPARTNO") "BRS133-902") (field (name "TOLERANCE") "+/-5%"))
      (libsource (lib "Altium_DB-Lib_Agile9.3") (part "RESISTOR SMT"))
    )
    (comp (ref "R72")
      (value "open")
      (footprint "0603")
      (fields (field (name "TOLERANCE") "+/-5%"))
      (libsource (lib "Altium_DB-Lib_Agile9.3") (part "RESISTOR SMT"))
    )
    (comp (ref "R73")
      (value "Resistor SMD 0603, 6.8 k Ohm, +/-1%, 1/10W")
      (footprint "0603")
      (fields (field (name "SMLPARTNO") "BRS131-682") (field (name "TOLERANCE") "+/-5%"))
      (libsource (lib "Altium_DB-Lib_Agile9.3") (part "RESISTOR SMT"))
    )
    (comp (ref "R74")
      (value "Resistor SMD 0603, 4.7 k Ohm, +/-5%, 1/10W")
      (footprint "0603")
      (fields (field (name "SMLPARTNO") "BRS133-472") (field (name "TOLERANCE") "+/-5%"))
      (libsource (lib "Altium_DB-Lib_Agile9.3") (part "RESISTOR SMT"))
    )
    (comp (ref "R75")
      (value "Resistor SMD 0603, 4.7 k Ohm, +/-5%, 1/10W")
      (footprint "0603")
      (fields (field (name "SMLPARTNO") "BRS133-472") (field (name "TOLERANCE") "+/-5%"))
      (libsource (lib "Altium_DB-Lib_Agile9.3") (part "RESISTOR SMT"))
    )
    (comp (ref "R76")
      (value "Resistor SMD 0603, 6.8 k Ohm, +/-1%, 1/10W")
      (footprint "0603")
      (fields (field (name "SMLPARTNO") "BRS131-682") (field (name "TOLERANCE") "+/-5%"))
      (libsource (lib "Altium_DB-Lib_Agile9.3") (part "RESISTOR SMT"))
    )
    (comp (ref "R77")
      (value "open")
      (footprint "0603")
      (fields (field (name "TOLERANCE") "+/-5%"))
      (libsource (lib "Altium_DB-Lib_Agile9.3") (part "RESISTOR SMT"))
    )
    (comp (ref "R78")
      (value "Resistor SMD 0603, 9.1 k Ohm, +/-5%, 1/10W")
      (footprint "0603")
      (fields (field (name "SMLPARTNO") "BRS131-912") (field (name "TOLERANCE") "+/-5%"))
      (libsource (lib "Altium_DB-Lib_Agile9.3") (part "RESISTOR SMT"))
    )
    (comp (ref "R79")
      (value "Resistor SMD 0603, 1.5 k Ohm, +/-5%, 1/10W")
      (footprint "0603")
      (fields (field (name "SMLPARTNO") "BRS131-152") (field (name "TOLERANCE") "+/-5%"))
      (libsource (lib "Altium_DB-Lib_Agile9.3") (part "RESISTOR SMT"))
    )
    (comp (ref "R80")
      (value "Resistor SMD 0603, 100 k Ohm, +/-5%, 1/10W")
      (footprint "0603")
      (fields (field (name "SMLPARTNO") "BRS131-104") (field (name "TOLERANCE") "+/-5%"))
      (libsource (lib "Altium_DB-Lib_Agile9.3") (part "RESISTOR SMT"))
    )
    (comp (ref "R81")
      (value "Resistor SMD 0603, 9.1 k Ohm, +/-5%, 1/10W")
      (footprint "0603")
      (fields (field (name "SMLPARTNO") "BRS131-912") (field (name "TOLERANCE") "+/-5%"))
      (libsource (lib "Altium_DB-Lib_Agile9.3") (part "RESISTOR SMT"))
    )
    (comp (ref "R82")
      (value "OPEN")
      (footprint "0603")
      (fields (field (name "TOLERANCE") "+/-5%"))
      (libsource (lib "Altium_DB-Lib_Agile9.3") (part "RESISTOR SMT"))
    )
    (comp (ref "R83")
      (value "Resistor SMD 0603, 6.8 k Ohm, +/-1%, 1/10W")
      (footprint "0603")
      (fields (field (name "SMLPARTNO") "BRS131-682") (field (name "TOLERANCE") "+/-5%"))
      (libsource (lib "Altium_DB-Lib_Agile9.3") (part "RESISTOR SMT"))
    )
    (comp (ref "R84")
      (value "Resistor SMD 0603, 4.7 k Ohm, +/-5%, 1/10W")
      (footprint "0603")
      (fields (field (name "SMLPARTNO") "BRS133-472") (field (name "TOLERANCE") "+/-5%"))
      (libsource (lib "Altium_DB-Lib_Agile9.3") (part "RESISTOR SMT"))
    )
    (comp (ref "R85")
      (value "Resistor SMD 0603, 4.7 k Ohm, +/-5%, 1/10W")
      (footprint "0603")
      (fields (field (name "SMLPARTNO") "BRS133-472") (field (name "TOLERANCE") "+/-5%"))
      (libsource (lib "Altium_DB-Lib_Agile9.3") (part "RESISTOR SMT"))
    )
    (comp (ref "R86")
      (value "Resistor SMD 0603, 6.8 k Ohm, +/-1%, 1/10W")
      (footprint "0603")
      (fields (field (name "SMLPARTNO") "BRS131-682") (field (name "TOLERANCE") "+/-5%"))
      (libsource (lib "Altium_DB-Lib_Agile9.3") (part "RESISTOR SMT"))
    )
    (comp (ref "R87")
      (value "OPEN")
      (footprint "0603")
      (fields (field (name "TOLERANCE") "+/-5%"))
      (libsource (lib "Altium_DB-Lib_Agile9.3") (part "RESISTOR SMT"))
    )
    (comp (ref "R88")
      (value "Resistor SMD 0603, 9.1 k Ohm, +/-5%, 1/10W")
      (footprint "0603")
      (fields (field (name "SMLPARTNO") "BRS131-912") (field (name "TOLERANCE") "+/-5%"))
      (libsource (lib "Altium_DB-Lib_Agile9.3") (part "RESISTOR SMT"))
    )
    (comp (ref "R89")
      (value "Resistor SMD 0603, 9.1 k Ohm, +/-5%, 1/10W")
      (footprint "0603")
      (fields (field (name "SMLPARTNO") "BRS131-912") (field (name "TOLERANCE") "+/-5%"))
      (libsource (lib "Altium_DB-Lib_Agile9.3") (part "RESISTOR SMT"))
    )
    (comp (ref "R90")
      (value "OPEN")
      (footprint "0603")
      (fields (field (name "TOLERANCE") "+/-5%"))
      (libsource (lib "Altium_DB-Lib_Agile9.3") (part "RESISTOR SMT"))
    )
    (comp (ref "R91")
      (value "Resistor SMD 0603, 6.8 k Ohm, +/-1%, 1/10W")
      (footprint "0603")
      (fields (field (name "SMLPARTNO") "BRS131-682") (field (name "TOLERANCE") "+/-5%"))
      (libsource (lib "Altium_DB-Lib_Agile9.3") (part "RESISTOR SMT"))
    )
    (comp (ref "R92")
      (value "Resistor SMD 0603, 4.7 k Ohm, +/-5%, 1/10W")
      (footprint "0603")
      (fields (field (name "SMLPARTNO") "BRS133-472") (field (name "TOLERANCE") "+/-5%"))
      (libsource (lib "Altium_DB-Lib_Agile9.3") (part "RESISTOR SMT"))
    )
    (comp (ref "R93")
      (value "Resistor SMD 0603, 4.7 k Ohm, +/-5%, 1/10W")
      (footprint "0603")
      (fields (field (name "SMLPARTNO") "BRS133-472") (field (name "TOLERANCE") "+/-5%"))
      (libsource (lib "Altium_DB-Lib_Agile9.3") (part "RESISTOR SMT"))
    )
    (comp (ref "R94")
      (value "Resistor SMD 0603, 6.8 k Ohm, +/-1%, 1/10W")
      (footprint "0603")
      (fields (field (name "SMLPARTNO") "BRS131-682") (field (name "TOLERANCE") "+/-5%"))
      (libsource (lib "Altium_DB-Lib_Agile9.3") (part "RESISTOR SMT"))
    )
    (comp (ref "R95")
      (value "OPEN")
      (footprint "0603")
      (fields (field (name "TOLERANCE") "+/-5%"))
      (libsource (lib "Altium_DB-Lib_Agile9.3") (part "RESISTOR SMT"))
    )
    (comp (ref "R96")
      (value "Resistor SMD 0603, 9.1 k Ohm, +/-5%, 1/10W")
      (footprint "0603")
      (fields (field (name "SMLPARTNO") "BRS131-912") (field (name "TOLERANCE") "+/-5%"))
      (libsource (lib "Altium_DB-Lib_Agile9.3") (part "RESISTOR SMT"))
    )
    (comp (ref "R97")
      (value "~")
      (footprint "0603")
      (description "Resistor SMD 0603, 0 Ohm, +/-5%, 1/10W")
      (fields (field (name "SMLPARTNO") "BRS132-000") (field (name "TOLERANCE") "+/-5%"))
      (libsource (lib "Altium_DB-Lib_Agile9.3") (part "RESISTOR SMT"))
    )
    (comp (ref "R98")
      (value "1Kohm")
      (footprint "0603")
      (description "Resistor SMD 0603, 1 k Ohm, +/-1%, 1/10W")
      (fields (field (name "SMLPARTNO") "BRS831-102") (field (name "TOLERANCE") "+/-1%"))
      (libsource (lib "Altium_DB-Lib_Agile9.3") (part "RESISTOR SMT"))
    )
    (comp (ref "R99")
      (value "1Kohm")
      (footprint "0603")
      (description "Resistor SMD 0603, 1 k Ohm, +/-1%, 1/10W")
      (fields (field (name "SMLPARTNO") "BRS831-102") (field (name "TOLERANCE") "+/-1%"))
      (libsource (lib "Altium_DB-Lib_Agile9.3") (part "RESISTOR SMT"))
    )
    (comp (ref "R100")
      (value "1Kohm")
      (footprint "0603")
      (description "Resistor SMD 0603, 1 k Ohm, +/-1%, 1/10W")
      (fields (field (name "SMLPARTNO") "BRS831-102") (field (name "TOLERANCE") "+/-1%"))
      (libsource (lib "Altium_DB-Lib_Agile9.3") (part "RESISTOR SMT"))
    )
    (comp (ref "R101")
      (value "1Kohm")
      (footprint "0603")
      (description "Resistor SMD 0603, 1 k Ohm, +/-1%, 1/10W")
      (fields (field (name "SMLPARTNO") "BRS831-102") (field (name "TOLERANCE") "+/-1%"))
      (libsource (lib "Altium_DB-Lib_Agile9.3") (part "RESISTOR SMT"))
    )
    (comp (ref "R102")
      (value "1Kohm")
      (footprint "0603")
      (description "Resistor SMD 0603, 1 k Ohm, +/-1%, 1/10W")
      (fields (field (name "SMLPARTNO") "BRS831-102") (field (name "TOLERANCE") "+/-1%"))
      (libsource (lib "Altium_DB-Lib_Agile9.3") (part "RESISTOR SMT"))
    )
    (comp (ref "R103")
      (value "1Kohm")
      (footprint "0603")
      (description "Resistor SMD 0603, 1 k Ohm, +/-1%, 1/10W")
      (fields (field (name "SMLPARTNO") "BRS831-102") (field (name "TOLERANCE") "+/-1%"))
      (libsource (lib "Altium_DB-Lib_Agile9.3") (part "RESISTOR SMT"))
    )
    (comp (ref "R104")
      (value "1Kohm")
      (footprint "0603")
      (description "Resistor SMD 0603, 1 k Ohm, +/-1%, 1/10W")
      (fields (field (name "SMLPARTNO") "BRS831-102") (field (name "TOLERANCE") "+/-1%"))
      (libsource (lib "Altium_DB-Lib_Agile9.3") (part "RESISTOR SMT"))
    )
    (comp (ref "R105")
      (value "1Kohm")
      (footprint "0603")
      (description "Resistor SMD 0603, 1 k Ohm, +/-1%, 1/10W")
      (fields (field (name "SMLPARTNO") "BRS831-102") (field (name "TOLERANCE") "+/-1%"))
      (libsource (lib "Altium_DB-Lib_Agile9.3") (part "RESISTOR SMT"))
    )
    (comp (ref "R106")
      (value "1Kohm")
      (footprint "0603")
      (description "Resistor SMD 0603, 1 k Ohm, +/-1%, 1/10W")
      (fields (field (name "SMLPARTNO") "BRS831-102") (field (name "TOLERANCE") "+/-1%"))
      (libsource (lib "Altium_DB-Lib_Agile9.3") (part "RESISTOR SMT"))
    )
    (comp (ref "R107")
      (value "~")
      (footprint "0603")
      (description "Resistor SMD 0603, 0 Ohm, +/-5%, 1/10W")
      (fields (field (name "SMLPARTNO") "BRS132-000") (field (name "TOLERANCE") "+/-5%"))
      (libsource (lib "Altium_DB-Lib_Agile9.3") (part "RESISTOR SMT"))
    )
    (comp (ref "R108")
      (value "~")
      (footprint "0603")
      (description "Resistor SMD 0603, 0 Ohm, +/-5%, 1/10W")
      (fields (field (name "SMLPARTNO") "BRS132-000") (field (name "TOLERANCE") "+/-5%"))
      (libsource (lib "Altium_DB-Lib_Agile9.3") (part "RESISTOR SMT"))
    )
    (comp (ref "R109")
      (value "~")
      (footprint "0603")
      (description "Resistor SMD 0603, 0 Ohm, +/-5%, 1/10W")
      (fields (field (name "SMLPARTNO") "BRS132-000") (field (name "TOLERANCE") "+/-5%"))
      (libsource (lib "Altium_DB-Lib_Agile9.3") (part "RESISTOR SMT"))
    )
    (comp (ref "R110")
      (value "~")
      (footprint "0603")
      (description "Resistor SMD 0603, 0 Ohm, +/-5%, 1/10W")
      (fields (field (name "SMLPARTNO") "BRS132-000") (field (name "TOLERANCE") "+/-5%"))
      (libsource (lib "Altium_DB-Lib_Agile9.3") (part "RESISTOR SMT"))
    )
    (comp (ref "R111")
      (value "~")
      (footprint "0603")
      (description "Resistor SMD 0603, 0 Ohm, +/-5%, 1/10W")
      (fields (field (name "SMLPARTNO") "BRS132-000") (field (name "TOLERANCE") "+/-5%"))
      (libsource (lib "Altium_DB-Lib_Agile9.3") (part "RESISTOR SMT"))
    )
    (comp (ref "R112")
      (value "~")
      (footprint "0603")
      (description "Resistor SMD 0603, 0 Ohm, +/-5%, 1/10W")
      (fields (field (name "SMLPARTNO") "BRS132-000") (field (name "TOLERANCE") "+/-5%"))
      (libsource (lib "Altium_DB-Lib_Agile9.3") (part "RESISTOR SMT"))
    )
    (comp (ref "R113")
      (value "~")
      (footprint "0603")
      (description "Resistor SMD 0603, 0 Ohm, +/-5%, 1/10W")
      (fields (field (name "SMLPARTNO") "BRS132-000") (field (name "TOLERANCE") "+/-5%"))
      (libsource (lib "Altium_DB-Lib_Agile9.3") (part "RESISTOR SMT"))
    )
    (comp (ref "R114")
      (value "~")
      (footprint "0603")
      (description "Resistor SMD 0603, 0 Ohm, +/-5%, 1/10W")
      (fields (field (name "SMLPARTNO") "BRS132-000") (field (name "TOLERANCE") "+/-5%"))
      (libsource (lib "Altium_DB-Lib_Agile9.3") (part "RESISTOR SMT"))
    )
    (comp (ref "R115")
      (value "~")
      (footprint "0603")
      (description "Resistor SMD 0603, 0 Ohm, +/-5%, 1/10W")
      (fields (field (name "SMLPARTNO") "BRS132-000") (field (name "TOLERANCE") "+/-5%"))
      (libsource (lib "Altium_DB-Lib_Agile9.3") (part "RESISTOR SMT"))
    )
    (comp (ref "R116")
      (value "~")
      (footprint "0603")
      (description "Resistor SMD 0603, 0 Ohm, +/-5%, 1/10W")
      (fields (field (name "SMLPARTNO") "BRS132-000") (field (name "TOLERANCE") "+/-5%"))
      (libsource (lib "Altium_DB-Lib_Agile9.3") (part "RESISTOR SMT"))
    )
    (comp (ref "R117")
      (value "~")
      (footprint "0603")
      (description "Resistor SMD 0603, 0 Ohm, +/-5%, 1/10W")
      (fields (field (name "SMLPARTNO") "BRS132-000") (field (name "TOLERANCE") "+/-5%"))
      (libsource (lib "Altium_DB-Lib_Agile9.3") (part "RESISTOR SMT"))
    )
    (comp (ref "R118")
      (value "~")
      (footprint "0603")
      (description "Resistor SMD 0603, 0 Ohm, +/-5%, 1/10W")
      (fields (field (name "SMLPARTNO") "BRS132-000") (field (name "TOLERANCE") "+/-5%"))
      (libsource (lib "Altium_DB-Lib_Agile9.3") (part "RESISTOR SMT"))
    )
    (comp (ref "R119")
      (value "1Kohm")
      (footprint "0603")
      (description "Resistor SMD 0603, 1 k Ohm, +/-1%, 1/10W")
      (fields (field (name "SMLPARTNO") "BRS831-102") (field (name "TOLERANCE") "+/-1%"))
      (libsource (lib "Altium_DB-Lib_Agile9.3") (part "RESISTOR SMT"))
    )
    (comp (ref "R120")
      (value "1Kohm")
      (footprint "0603")
      (description "Resistor SMD 0603, 1 k Ohm, +/-1%, 1/10W")
      (fields (field (name "SMLPARTNO") "BRS831-102") (field (name "TOLERANCE") "+/-1%"))
      (libsource (lib "Altium_DB-Lib_Agile9.3") (part "RESISTOR SMT"))
    )
    (comp (ref "R121")
      (value "1Kohm")
      (footprint "0603")
      (description "Resistor SMD 0603, 1 k Ohm, +/-1%, 1/10W")
      (fields (field (name "SMLPARTNO") "BRS831-102") (field (name "TOLERANCE") "+/-1%"))
      (libsource (lib "Altium_DB-Lib_Agile9.3") (part "RESISTOR SMT"))
    )
    (comp (ref "R122")
      (value "1Kohm")
      (footprint "0603")
      (description "Resistor SMD 0603, 1 k Ohm, +/-1%, 1/10W")
      (fields (field (name "SMLPARTNO") "BRS831-102") (field (name "TOLERANCE") "+/-1%"))
      (libsource (lib "Altium_DB-Lib_Agile9.3") (part "RESISTOR SMT"))
    )
    (comp (ref "R123")
      (value "1Kohm")
      (footprint "0603")
      (description "Resistor SMD 0603, 1 k Ohm, +/-1%, 1/10W")
      (fields (field (name "SMLPARTNO") "BRS831-102") (field (name "TOLERANCE") "+/-1%"))
      (libsource (lib "Altium_DB-Lib_Agile9.3") (part "RESISTOR SMT"))
    )
    (comp (ref "R124")
      (value "Resistor SMD 0603, 0 Ohm, +/-5%, 1/10W")
      (footprint "0603")
      (fields (field (name "SMLPARTNO") "BRS133-000") (field (name "TOLERANCE") "+/-5%"))
      (libsource (lib "Altium_DB-Lib_Agile9.3") (part "RESISTOR SMT"))
    )
    (comp (ref "R125")
      (value "Resistor SMD 0603, 0 Ohm, +/-5%, 1/10W")
      (footprint "0603")
      (fields (field (name "SMLPARTNO") "BRS133-000") (field (name "TOLERANCE") "+/-5%"))
      (libsource (lib "Altium_DB-Lib_Agile9.3") (part "RESISTOR SMT"))
    )
    (comp (ref "R126")
      (value "1Kohm")
      (footprint "0603")
      (description "Resistor SMD 0603, 1 k Ohm, +/-1%, 1/10W")
      (fields (field (name "SMLPARTNO") "BRS831-102") (field (name "TOLERANCE") "+/-1%"))
      (libsource (lib "Altium_DB-Lib_Agile9.3") (part "RESISTOR SMT"))
    )
    (comp (ref "R127")
      (value "Resistor SMD 0603, 0 Ohm, +/-5%, 1/10W")
      (footprint "0603")
      (fields (field (name "SMLPARTNO") "BRS133-000") (field (name "TOLERANCE") "+/-5%"))
      (libsource (lib "Altium_DB-Lib_Agile9.3") (part "RESISTOR SMT"))
    )
    (comp (ref "R128")
      (value "1Kohm")
      (footprint "0603")
      (description "Resistor SMD 0603, 1 k Ohm, +/-1%, 1/10W")
      (fields (field (name "SMLPARTNO") "BRS831-102") (field (name "TOLERANCE") "+/-1%"))
      (libsource (lib "Altium_DB-Lib_Agile9.3") (part "RESISTOR SMT"))
    )
    (comp (ref "R129")
      (value "1Kohm")
      (footprint "0603")
      (description "Resistor SMD 0603, 1 k Ohm, +/-1%, 1/10W")
      (fields (field (name "SMLPARTNO") "BRS831-102") (field (name "TOLERANCE") "+/-1%"))
      (libsource (lib "Altium_DB-Lib_Agile9.3") (part "RESISTOR SMT"))
    )
    (comp (ref "R130")
      (value "Resistor SMD 0603, 0 Ohm, +/-5%, 1/10W")
      (footprint "0603")
      (fields (field (name "SMLPARTNO") "BRS133-000") (field (name "TOLERANCE") "+/-5%"))
      (libsource (lib "Altium_DB-Lib_Agile9.3") (part "RESISTOR SMT"))
    )
    (comp (ref "R131")
      (value "Resistor SMD 0603, 4.7 k Ohm, +/-5%, 1/10W")
      (footprint "0603")
      (fields (field (name "SMLPARTNO") "BRS133-472") (field (name "TOLERANCE") "+/-1%"))
      (libsource (lib "Altium_DB-Lib_Agile9.3") (part "RESISTOR SMT"))
    )
    (comp (ref "R132")
      (value "Resistor SMD 0603, 4.7 k Ohm, +/-5%, 1/10W")
      (footprint "0603")
      (fields (field (name "SMLPARTNO") "BRS133-472") (field (name "TOLERANCE") "+/-1%"))
      (libsource (lib "Altium_DB-Lib_Agile9.3") (part "RESISTOR SMT"))
    )
    (comp (ref "R133")
      (value "Resistor SMD 0603, 0 Ohm, +/-5%, 1/10W")
      (footprint "0603")
      (fields (field (name "SMLPARTNO") "BRS133-000") (field (name "TOLERANCE") "+/-5%"))
      (libsource (lib "Altium_DB-Lib_Agile9.3") (part "RESISTOR SMT"))
    )
    (comp (ref "R134")
      (value "Resistor SMD 0603, 0 Ohm, +/-5%, 1/10W")
      (footprint "0603")
      (fields (field (name "SMLPARTNO") "BRS133-000") (field (name "TOLERANCE") "+/-5%"))
      (libsource (lib "Altium_DB-Lib_Agile9.3") (part "RESISTOR SMT"))
    )
    (comp (ref "TP0") (value "TEST PAD") (footprint "TP") (libsource (lib "Extra Part") (part "TEST PAD")))
    (comp (ref "TP1") (value "TEST PAD") (footprint "TP") (libsource (lib "Extra Part") (part "TEST PAD")))
    (comp (ref "TP2") (value "TEST PAD") (footprint "TP") (libsource (lib "Extra Part") (part "TEST PAD")))
    (comp (ref "TP3") (value "TEST PAD") (footprint "TP") (libsource (lib "Extra Part") (part "TEST PAD")))
    (comp (ref "TP4") (value "TEST PAD") (footprint "TP") (libsource (lib "Extra Part") (part "TEST PAD")))
    (comp (ref "TP5") (value "TEST PAD") (footprint "TP") (libsource (lib "Extra Part") (part "TEST PAD")))
    (comp (ref "TP6") (value "TEST PAD") (footprint "TP") (libsource (lib "Extra Part") (part "TEST PAD")))
    (comp (ref "U1")
      (value "74ACT573SJ")
      (footprint "sol-20")
      (description "Octal Latch with 3-State Output")
      (fields (field (name "PUBLISHER") "Altium Limited"))
      (libsource (lib "FSC Logic Latch") (part "74ACT573SJ"))
    )
    (comp (ref "U2")
      (value "4067")
      (footprint "SSOP-24")
      (description "MUX-74HC4067")
      (libsource (lib "CustomLibrary") (part "MUX-74HC4067"))
    )
    (comp (ref "U3")
      (value "ISO7640")
      (footprint "SOIC-16")
      (description "IC digital isolator SMD SOIC-16, ISO7640")
      (fields (field (name "SMLPARTNO") "BIS116-038"))
      (libsource (lib "") (part "ISO7640_1"))
    )
    (comp (ref "U4")
      (value "ISO7640")
      (footprint "SOIC-16")
      (description "IC digital isolator SMD SOIC-16, ISO7640")
      (fields (field (name "SMLPARTNO") "BIS116-038"))
      (libsource (lib "Altium_DB-Lib_Agile9.3") (part "ISO7640"))
    )
  )
  (nets
    (net (code "1") (name "+1.8") (class "Default")
      (node (ref "IC1") (pin "4") (pinfunction "4_4") (pintype "passive"))
      (node (ref "IC2") (pin "4") (pinfunction "4_4") (pintype "passive"))
      (node (ref "IC3") (pin "4") (pinfunction "4_4") (pintype "passive"))
      (node (ref "IC4") (pin "4") (pinfunction "4_4") (pintype "passive"))
      (node (ref "IC5") (pin "1") (pinfunction "1_1") (pintype "passive"))
      (node (ref "IC5") (pin "2") (pinfunction "2_2") (pintype "passive"))
      (node (ref "R16") (pin "2") (pinfunction "2_2") (pintype "passive"))
      (node (ref "R26") (pin "2") (pinfunction "2_2") (pintype "passive"))
      (node (ref "R29") (pin "2") (pinfunction "2_2") (pintype "passive"))
      (node (ref "R34") (pin "2") (pinfunction "2_2") (pintype "passive"))
      (node (ref "R37") (pin "2") (pinfunction "2_2") (pintype "passive"))
      (node (ref "R39") (pin "2") (pinfunction "2_2") (pintype "passive"))
      (node (ref "R40") (pin "2") (pinfunction "2_2") (pintype "passive"))
      (node (ref "R5") (pin "2") (pinfunction "2_2") (pintype "passive"))
      (node (ref "R61") (pin "1") (pinfunction "1_1") (pintype "passive"))
      (node (ref "R64") (pin "1") (pinfunction "1_1") (pintype "passive"))
      (node (ref "R73") (pin "1") (pinfunction "1_1") (pintype "passive"))
      (node (ref "R76") (pin "1") (pinfunction "1_1") (pintype "passive"))
      (node (ref "R83") (pin "1") (pinfunction "1_1") (pintype "passive"))
      (node (ref "R86") (pin "1") (pinfunction "1_1") (pintype "passive"))
      (node (ref "R91") (pin "1") (pinfunction "1_1") (pintype "passive"))
      (node (ref "R94") (pin "1") (pinfunction "1_1") (pintype "passive"))
      (node (ref "TP5") (pin "1") (pintype "passive"))
    )
    (net (code "2") (name "/ADC0") (class "Default")
      (node (ref "P9") (pin "39") (pinfunction "39_39") (pintype "passive"))
      (node (ref "R100") (pin "1") (pinfunction "1_1") (pintype "passive"))
    )
    (net (code "3") (name "/ADC1") (class "Default")
      (node (ref "P9") (pin "40") (pinfunction "40_40") (pintype "passive"))
      (node (ref "R101") (pin "1") (pinfunction "1_1") (pintype "passive"))
    )
    (net (code "4") (name "/ADC2") (class "Default")
      (node (ref "P9") (pin "37") (pinfunction "37_37") (pintype "passive"))
      (node (ref "R102") (pin "1") (pinfunction "1_1") (pintype "passive"))
    )
    (net (code "5") (name "/ADC3") (class "Default")
      (node (ref "P9") (pin "38") (pinfunction "38_38") (pintype "passive"))
      (node (ref "R103") (pin "1") (pinfunction "1_1") (pintype "passive"))
    )
    (net (code "6") (name "/ADC4") (class "Default")
      (node (ref "P9") (pin "33") (pinfunction "33_33") (pintype "passive"))
      (node (ref "R104") (pin "1") (pinfunction "1_1") (pintype "passive"))
    )
    (net (code "7") (name "/ADC5") (class "Default")
      (node (ref "P9") (pin "36") (pinfunction "36_36") (pintype "passive"))
      (node (ref "R105") (pin "1") (pinfunction "1_1") (pintype "passive"))
    )
    (net (code "8") (name "/ADC6") (class "Default")
      (node (ref "P9") (pin "35") (pinfunction "35_35") (pintype "passive"))
      (node (ref "R106") (pin "1") (pinfunction "1_1") (pintype "passive"))
    )
    (net (code "9") (name "/BBB_SEL0") (class "Default")
      (node (ref "R107") (pin "2") (pinfunction "2_2") (pintype "passive"))
      (node (ref "R108") (pin "2") (pinfunction "2_2") (pintype "passive"))
      (node (ref "R109") (pin "2") (pinfunction "2_2") (pintype "passive"))
      (node (ref "U1") (pin "2") (pinfunction "D1_2") (pintype "input"))
    )
    (net (code "10") (name "/BBB_SEL1") (class "Default")
      (node (ref "R110") (pin "2") (pinfunction "2_2") (pintype "passive"))
      (node (ref "R111") (pin "2") (pinfunction "2_2") (pintype "passive"))
      (node (ref "R112") (pin "2") (pinfunction "2_2") (pintype "passive"))
      (node (ref "U1") (pin "3") (pinfunction "D2_3") (pintype "input"))
    )
    (net (code "11") (name "/BBB_SEL2") (class "Default")
      (node (ref "R113") (pin "2") (pinfunction "2_2") (pintype "passive"))
      (node (ref "R114") (pin "2") (pinfunction "2_2") (pintype "passive"))
      (node (ref "R115") (pin "2") (pinfunction "2_2") (pintype "passive"))
      (node (ref "U1") (pin "4") (pinfunction "D3_4") (pintype "input"))
    )
    (net (code "12") (name "/BBB_SEL3") (class "Default")
      (node (ref "R116") (pin "2") (pinfunction "2_2") (pintype "passive"))
      (node (ref "R117") (pin "2") (pinfunction "2_2") (pintype "passive"))
      (node (ref "R118") (pin "2") (pinfunction "2_2") (pintype "passive"))
      (node (ref "U1") (pin "5") (pinfunction "D4_5") (pintype "input"))
    )
    (net (code "13") (name "/EN6595_2") (class "Default")
      (node (ref "P8") (pin "8") (pinfunction "8_8") (pintype "passive"))
      (node (ref "R120") (pin "2") (pinfunction "2_2") (pintype "passive"))
    )
    (net (code "14") (name "/IN0") (class "Default")
      (node (ref "H2") (pin "1") (pinfunction "1_1") (pintype "passive"))
      (node (ref "R81") (pin "1") (pinfunction "1_1") (pintype "passive"))
      (node (ref "R82") (pin "1") (pinfunction "1_1") (pintype "passive"))
    )
    (net (code "15") (name "/IN1") (class "Default")
      (node (ref "H2") (pin "2") (pinfunction "2_2") (pintype "passive"))
      (node (ref "R87") (pin "1") (pinfunction "1_1") (pintype "passive"))
      (node (ref "R88") (pin "1") (pinfunction "1_1") (pintype "passive"))
    )
    (net (code "16") (name "/IN2") (class "Default")
      (node (ref "H2") (pin "3") (pinfunction "3_3") (pintype "passive"))
      (node (ref "R28") (pin "2") (pinfunction "2_2") (pintype "passive"))
      (node (ref "R30") (pin "1") (pinfunction "1_1") (pintype "passive"))
    )
    (net (code "17") (name "/IN3") (class "Default")
      (node (ref "H2") (pin "4") (pinfunction "4_4") (pintype "passive"))
      (node (ref "R23") (pin "2") (pinfunction "2_2") (pintype "passive"))
      (node (ref "R24") (pin "2") (pinfunction "2_2") (pintype "passive"))
    )
    (net (code "18") (name "/IN4") (class "Default")
      (node (ref "H2") (pin "5") (pinfunction "5_5") (pintype "passive"))
      (node (ref "R59") (pin "1") (pinfunction "1_1") (pintype "passive"))
      (node (ref "R60") (pin "1") (pinfunction "1_1") (pintype "passive"))
    )
    (net (code "19") (name "/IN5") (class "Default")
      (node (ref "H2") (pin "6") (pinfunction "6_6") (pintype "passive"))
      (node (ref "R65") (pin "1") (pinfunction "1_1") (pintype "passive"))
      (node (ref "R66") (pin "1") (pinfunction "1_1") (pintype "passive"))
    )
    (net (code "20") (name "/IN6") (class "Default")
      (node (ref "H2") (pin "7") (pinfunction "7_7") (pintype "passive"))
      (node (ref "R8") (pin "2") (pinfunction "2_2") (pintype "passive"))
      (node (ref "R9") (pin "1") (pinfunction "1_1") (pintype "passive"))
    )
    (net (code "21") (name "/IN7") (class "Default")
      (node (ref "H2") (pin "8") (pinfunction "8_8") (pintype "passive"))
      (node (ref "R3") (pin "2") (pinfunction "2_2") (pintype "passive"))
      (node (ref "R4") (pin "2") (pinfunction "2_2") (pintype "passive"))
    )
    (net (code "22") (name "/IN8") (class "Default")
      (node (ref "H2") (pin "9") (pinfunction "9_9") (pintype "passive"))
      (node (ref "R89") (pin "1") (pinfunction "1_1") (pintype "passive"))
      (node (ref "R90") (pin "1") (pinfunction "1_1") (pintype "passive"))
    )
    (net (code "23") (name "/IN9") (class "Default")
      (node (ref "H2") (pin "10") (pinfunction "10_10") (pintype "passive"))
      (node (ref "R95") (pin "1") (pinfunction "1_1") (pintype "passive"))
      (node (ref "R96") (pin "1") (pinfunction "1_1") (pintype "passive"))
    )
    (net (code "24") (name "/IN10") (class "Default")
      (node (ref "H2") (pin "11") (pinfunction "11_11") (pintype "passive"))
      (node (ref "R31") (pin "2") (pinfunction "2_2") (pintype "passive"))
      (node (ref "R32") (pin "2") (pinfunction "2_2") (pintype "passive"))
    )
    (net (code "25") (name "/IN11") (class "Default")
      (node (ref "H2") (pin "12") (pinfunction "12_12") (pintype "passive"))
      (node (ref "R36") (pin "2") (pinfunction "2_2") (pintype "passive"))
      (node (ref "R38") (pin "1") (pinfunction "1_1") (pintype "passive"))
    )
    (net (code "26") (name "/IN12") (class "Default")
      (node (ref "H2") (pin "13") (pinfunction "13_13") (pintype "passive"))
      (node (ref "R71") (pin "1") (pinfunction "1_1") (pintype "passive"))
      (node (ref "R72") (pin "1") (pinfunction "1_1") (pintype "passive"))
    )
    (net (code "27") (name "/IN13") (class "Default")
      (node (ref "H2") (pin "14") (pinfunction "14_14") (pintype "passive"))
      (node (ref "R77") (pin "1") (pinfunction "1_1") (pintype "passive"))
      (node (ref "R78") (pin "1") (pinfunction "1_1") (pintype "passive"))
    )
    (net (code "28") (name "/IN14") (class "Default")
      (node (ref "H2") (pin "15") (pinfunction "15_15") (pintype "passive"))
      (node (ref "R19") (pin "2") (pinfunction "2_2") (pintype "passive"))
      (node (ref "R20") (pin "1") (pinfunction "1_1") (pintype "passive"))
    )
    (net (code "29") (name "/IN15") (class "Default")
      (node (ref "H2") (pin "16") (pinfunction "16_16") (pintype "passive"))
      (node (ref "R14") (pin "2") (pinfunction "2_2") (pintype "passive"))
      (node (ref "R15") (pin "2") (pinfunction "2_2") (pintype "passive"))
    )
    (net (code "30") (name "/LATCH1") (class "Default")
      (node (ref "R119") (pin "1") (pinfunction "1_1") (pintype "passive"))
      (node (ref "R120") (pin "1") (pinfunction "1_1") (pintype "passive"))
      (node (ref "R121") (pin "1") (pinfunction "1_1") (pintype "passive"))
      (node (ref "R122") (pin "1") (pinfunction "1_1") (pintype "passive"))
      (node (ref "R123") (pin "1") (pinfunction "1_1") (pintype "passive"))
      (node (ref "R126") (pin "1") (pinfunction "1_1") (pintype "passive"))
      (node (ref "R128") (pin "1") (pinfunction "1_1") (pintype "passive"))
      (node (ref "R129") (pin "1") (pinfunction "1_1") (pintype "passive"))
      (node (ref "R97") (pin "1") (pinfunction "1_1") (pintype "passive"))
      (node (ref "U1") (pin "11") (pinfunction "LE_11") (pintype "input"))
    )
    (net (code "31") (name "/P8-14") (class "Default")
      (node (ref "P8") (pin "14") (pinfunction "14_14") (pintype "passive"))
      (node (ref "R99") (pin "1") (pinfunction "1_1") (pintype "passive"))
    )
    (net (code "32") (name "/P8_7") (class "Default")
      (node (ref "P8") (pin "7") (pinfunction "7_7") (pintype "passive"))
      (node (ref "R119") (pin "2") (pinfunction "2_2") (pintype "passive"))
    )
    (net (code "33") (name "/P8_9") (class "Default")
      (node (ref "P8") (pin "9") (pinfunction "9_9") (pintype "passive"))
      (node (ref "R121") (pin "2") (pinfunction "2_2") (pintype "passive"))
    )
    (net (code "34") (name "/P8_10") (class "Default")
      (node (ref "P8") (pin "10") (pinfunction "10_10") (pintype "passive"))
      (node (ref "R122") (pin "2") (pinfunction "2_2") (pintype "passive"))
    )
    (net (code "35") (name "/P8_12") (class "Default")
      (node (ref "P8") (pin "12") (pinfunction "12_12") (pintype "passive"))
    )
    (net (code "36") (name "/P8_16") (class "Default")
      (node (ref "P8") (pin "16") (pinfunction "16_16") (pintype "passive"))
    )
    (net (code "37") (name "/P8_18") (class "Default")
      (node (ref "P8") (pin "18") (pinfunction "18_18") (pintype "passive"))
      (node (ref "R114") (pin "1") (pinfunction "1_1") (pintype "passive"))
    )
    (net (code "38") (name "/P9-24") (class "Default")
      (node (ref "P9") (pin "24") (pinfunction "24_24") (pintype "passive"))
      (node (ref "R98") (pin "1") (pinfunction "1_1") (pintype "passive"))
      (node (ref "TP0") (pin "1") (pintype "passive"))
      (node (ref "U2") (pin "15") (pinfunction "~{EN}_15") (pintype "input"))
    )
    (net (code "39") (name "/P9_11") (class "Default")
      (node (ref "P9") (pin "11") (pinfunction "11_11") (pintype "passive"))
      (node (ref "R107") (pin "1") (pinfunction "1_1") (pintype "passive"))
    )
    (net (code "40") (name "/P9_12") (class "Default")
      (node (ref "P9") (pin "12") (pinfunction "12_12") (pintype "passive"))
      (node (ref "R111") (pin "1") (pinfunction "1_1") (pintype "passive"))
      (node (ref "R123") (pin "2") (pinfunction "2_2") (pintype "passive"))
    )
    (net (code "41") (name "/P9_13") (class "Default")
      (node (ref "P9") (pin "13") (pinfunction "13_13") (pintype "passive"))
      (node (ref "R110") (pin "1") (pinfunction "1_1") (pintype "passive"))
      (node (ref "R113") (pin "1") (pinfunction "1_1") (pintype "passive"))
    )
    (net (code "42") (name "/P9_14") (class "Default")
      (node (ref "P9") (pin "14") (pinfunction "14_14") (pintype "passive"))
      (node (ref "R115") (pin "1") (pinfunction "1_1") (pintype "passive"))
      (node (ref "R117") (pin "1") (pinfunction "1_1") (pintype "passive"))
    )
    (net (code "43") (name "/P9_15") (class "Default")
      (node (ref "P9") (pin "15") (pinfunction "15_15") (pintype "passive"))
      (node (ref "R108") (pin "1") (pinfunction "1_1") (pintype "passive"))
      (node (ref "R116") (pin "1") (pinfunction "1_1") (pintype "passive"))
      (node (ref "R126") (pin "2") (pinfunction "2_2") (pintype "passive"))
    )
    (net (code "44") (name "/P9_16") (class "Default")
      (node (ref "P9") (pin "16") (pinfunction "16_16") (pintype "passive"))
      (node (ref "R128") (pin "2") (pinfunction "2_2") (pintype "passive"))
    )
    (net (code "45") (name "/P9_17") (class "Default")
      (node (ref "P9") (pin "17") (pinfunction "17_17") (pintype "passive"))
      (node (ref "R129") (pin "2") (pinfunction "2_2") (pintype "passive"))
    )
    (net (code "46") (name "/PIN1") (class "Default")
      (node (ref "J1") (pin "1") (pinfunction "1_1") (pintype "passive"))
      (node (ref "J2") (pin "1") (pinfunction "1_1") (pintype "passive"))
    )
    (net (code "47") (name "/PIN2") (class "Default")
      (node (ref "J1") (pin "4") (pinfunction "4_4") (pintype "passive"))
      (node (ref "J2") (pin "2") (pinfunction "2_2") (pintype "passive"))
      (node (ref "R133") (pin "2") (pinfunction "2_2") (pintype "passive"))
    )
    (net (code "48") (name "/PIN3") (class "Default")
      (node (ref "J1") (pin "5") (pinfunction "5_5") (pintype "passive"))
      (node (ref "J2") (pin "3") (pinfunction "3_3") (pintype "passive"))
      (node (ref "R134") (pin "2") (pinfunction "2_2") (pintype "passive"))
    )
    (net (code "49") (name "/S0") (class "Default")
      (node (ref "C1") (pin "1") (pinfunction "1_1") (pintype "passive"))
      (node (ref "IC3") (pin "1") (pinfunction "1_1") (pintype "passive"))
      (node (ref "R49") (pin "1") (pinfunction "1_1") (pintype "passive"))
      (node (ref "R53") (pin "1") (pinfunction "1_1") (pintype "passive"))
      (node (ref "U2") (pin "9") (pinfunction "I0_9") (pintype "bidirectional"))
    )
    (net (code "50") (name "/S1") (class "Default")
      (node (ref "C2") (pin "1") (pinfunction "1_1") (pintype "passive"))
      (node (ref "IC3") (pin "7") (pinfunction "7_7") (pintype "passive"))
      (node (ref "R50") (pin "1") (pinfunction "1_1") (pintype "passive"))
      (node (ref "R54") (pin "2") (pinfunction "2_2") (pintype "passive"))
      (node (ref "U2") (pin "8") (pinfunction "I1_8") (pintype "bidirectional"))
    )
    (net (code "51") (name "/S2") (class "Default")
      (node (ref "C3") (pin "1") (pinfunction "1_1") (pintype "passive"))
      (node (ref "IC3") (pin "8") (pinfunction "8_8") (pintype "passive"))
      (node (ref "R42") (pin "2") (pinfunction "2_2") (pintype "passive"))
      (node (ref "R46") (pin "1") (pinfunction "1_1") (pintype "passive"))
      (node (ref "U2") (pin "7") (pinfunction "I2_7") (pintype "bidirectional"))
    )
    (net (code "52") (name "/S3") (class "Default")
      (node (ref "C4") (pin "1") (pinfunction "1_1") (pintype "passive"))
      (node (ref "IC3") (pin "14") (pinfunction "14_14") (pintype "passive"))
      (node (ref "R41") (pin "1") (pinfunction "1_1") (pintype "passive"))
      (node (ref "R45") (pin "1") (pinfunction "1_1") (pintype "passive"))
      (node (ref "U2") (pin "6") (pinfunction "I3_6") (pintype "bidirectional"))
    )
    (net (code "53") (name "/S4") (class "Default")
      (node (ref "C5") (pin "1") (pinfunction "1_1") (pintype "passive"))
      (node (ref "IC1") (pin "1") (pinfunction "1_1") (pintype "passive"))
      (node (ref "R57") (pin "2") (pinfunction "2_2") (pintype "passive"))
      (node (ref "R58") (pin "2") (pinfunction "2_2") (pintype "passive"))
      (node (ref "U2") (pin "5") (pinfunction "I4_5") (pintype "bidirectional"))
    )
    (net (code "54") (name "/S5") (class "Default")
      (node (ref "C6") (pin "1") (pinfunction "1_1") (pintype "passive"))
      (node (ref "IC1") (pin "7") (pinfunction "7_7") (pintype "passive"))
      (node (ref "R67") (pin "1") (pinfunction "1_1") (pintype "passive"))
      (node (ref "R68") (pin "1") (pinfunction "1_1") (pintype "passive"))
      (node (ref "U2") (pin "4") (pinfunction "I5_4") (pintype "bidirectional"))
    )
    (net (code "55") (name "/S6") (class "Default")
      (node (ref "C7") (pin "1") (pinfunction "1_1") (pintype "passive"))
      (node (ref "IC1") (pin "8") (pinfunction "8_8") (pintype "passive"))
      (node (ref "R10") (pin "1") (pinfunction "1_1") (pintype "passive"))
      (node (ref "R11") (pin "1") (pinfunction "1_1") (pintype "passive"))
      (node (ref "U2") (pin "3") (pinfunction "I6_3") (pintype "bidirectional"))
    )
    (net (code "56") (name "/S7") (class "Default")
      (node (ref "C8") (pin "1") (pinfunction "1_1") (pintype "passive"))
      (node (ref "IC1") (pin "14") (pinfunction "14_14") (pintype "passive"))
      (node (ref "R1") (pin "1") (pinfunction "1_1") (pintype "passive"))
      (node (ref "R2") (pin "1") (pinfunction "1_1") (pintype "passive"))
      (node (ref "U2") (pin "2") (pinfunction "I7_2") (pintype "bidirectional"))
    )
    (net (code "57") (name "/S8") (class "Default")
      (node (ref "C9") (pin "1") (pinfunction "1_1") (pintype "passive"))
      (node (ref "IC4") (pin "1") (pinfunction "1_1") (pintype "passive"))
      (node (ref "R51") (pin "1") (pinfunction "1_1") (pintype "passive"))
      (node (ref "R55") (pin "1") (pinfunction "1_1") (pintype "passive"))
      (node (ref "U2") (pin "23") (pinfunction "I8_23") (pintype "bidirectional"))
    )
    (net (code "58") (name "/S9") (class "Default")
      (node (ref "C10") (pin "1") (pinfunction "1_1") (pintype "passive"))
      (node (ref "IC4") (pin "7") (pinfunction "7_7") (pintype "passive"))
      (node (ref "R52") (pin "1") (pinfunction "1_1") (pintype "passive"))
      (node (ref "R56") (pin "2") (pinfunction "2_2") (pintype "passive"))
      (node (ref "U2") (pin "22") (pinfunction "I9_22") (pintype "bidirectional"))
    )
    (net (code "59") (name "/S10") (class "Default")
      (node (ref "C11") (pin "1") (pinfunction "1_1") (pintype "passive"))
      (node (ref "IC4") (pin "8") (pinfunction "8_8") (pintype "passive"))
      (node (ref "R44") (pin "2") (pinfunction "2_2") (pintype "passive"))
      (node (ref "R48") (pin "1") (pinfunction "1_1") (pintype "passive"))
      (node (ref "U2") (pin "21") (pinfunction "I10_21") (pintype "bidirectional"))
    )
    (net (code "60") (name "/S11") (class "Default")
      (node (ref "C12") (pin "1") (pinfunction "1_1") (pintype "passive"))
      (node (ref "IC4") (pin "14") (pinfunction "14_14") (pintype "passive"))
      (node (ref "R43") (pin "1") (pinfunction "1_1") (pintype "passive"))
      (node (ref "R47") (pin "1") (pinfunction "1_1") (pintype "passive"))
      (node (ref "U2") (pin "20") (pinfunction "I11_20") (pintype "bidirectional"))
    )
    (net (code "61") (name "/S12") (class "Default")
      (node (ref "C13") (pin "1") (pinfunction "1_1") (pintype "passive"))
      (node (ref "IC2") (pin "1") (pinfunction "1_1") (pintype "passive"))
      (node (ref "R69") (pin "2") (pinfunction "2_2") (pintype "passive"))
      (node (ref "R70") (pin "2") (pinfunction "2_2") (pintype "passive"))
      (node (ref "U2") (pin "19") (pinfunction "I12_19") (pintype "bidirectional"))
    )
    (net (code "62") (name "/S13") (class "Default")
      (node (ref "C14") (pin "1") (pinfunction "1_1") (pintype "passive"))
      (node (ref "IC2") (pin "7") (pinfunction "7_7") (pintype "passive"))
      (node (ref "R79") (pin "1") (pinfunction "1_1") (pintype "passive"))
      (node (ref "R80") (pin "1") (pinfunction "1_1") (pintype "passive"))
      (node (ref "U2") (pin "18") (pinfunction "I13_18") (pintype "bidirectional"))
    )
    (net (code "63") (name "/S14") (class "Default")
      (node (ref "C15") (pin "1") (pinfunction "1_1") (pintype "passive"))
      (node (ref "IC2") (pin "8") (pinfunction "8_8") (pintype "passive"))
      (node (ref "R21") (pin "1") (pinfunction "1_1") (pintype "passive"))
      (node (ref "R22") (pin "1") (pinfunction "1_1") (pintype "passive"))
      (node (ref "U2") (pin "17") (pinfunction "I14_17") (pintype "bidirectional"))
    )
    (net (code "64") (name "/S15") (class "Default")
      (node (ref "C16") (pin "1") (pinfunction "1_1") (pintype "passive"))
      (node (ref "IC2") (pin "14") (pinfunction "14_14") (pintype "passive"))
      (node (ref "R12") (pin "1") (pinfunction "1_1") (pintype "passive"))
      (node (ref "R13") (pin "1") (pinfunction "1_1") (pintype "passive"))
      (node (ref "U2") (pin "16") (pinfunction "I15_16") (pintype "bidirectional"))
    )
    (net (code "65") (name "/SEL0") (class "Default")
      (node (ref "TP6") (pin "1") (pintype "passive"))
      (node (ref "U1") (pin "19") (pinfunction "Q1_19") (pintype "tri_state"))
      (node (ref "U2") (pin "10") (pinfunction "S0_10") (pintype "input"))
    )
    (net (code "66") (name "/SEL1") (class "Default")
      (node (ref "TP1") (pin "1") (pintype "passive"))
      (node (ref "U1") (pin "18") (pinfunction "Q2_18") (pintype "tri_state"))
      (node (ref "U2") (pin "11") (pinfunction "S1_11") (pintype "input"))
    )
    (net (code "67") (name "/SEL2") (class "Default")
      (node (ref "TP2") (pin "1") (pintype "passive"))
      (node (ref "U1") (pin "17") (pinfunction "Q3_17") (pintype "tri_state"))
      (node (ref "U2") (pin "14") (pinfunction "S2_14") (pintype "input"))
    )
    (net (code "68") (name "/SEL3") (class "Default")
      (node (ref "TP3") (pin "1") (pintype "passive"))
      (node (ref "U1") (pin "16") (pinfunction "Q4_16") (pintype "tri_state"))
      (node (ref "U2") (pin "13") (pinfunction "S3_13") (pintype "input"))
    )
    (net (code "69") (name "/SIG1") (class "Default")
      (node (ref "R100") (pin "2") (pinfunction "2_2") (pintype "passive"))
      (node (ref "R101") (pin "2") (pinfunction "2_2") (pintype "passive"))
      (node (ref "R102") (pin "2") (pinfunction "2_2") (pintype "passive"))
      (node (ref "R103") (pin "2") (pinfunction "2_2") (pintype "passive"))
      (node (ref "R104") (pin "2") (pinfunction "2_2") (pintype "passive"))
      (node (ref "R105") (pin "2") (pinfunction "2_2") (pintype "passive"))
      (node (ref "R106") (pin "2") (pinfunction "2_2") (pintype "passive"))
      (node (ref "R99") (pin "2") (pinfunction "2_2") (pintype "passive"))
      (node (ref "TP4") (pin "1") (pintype "passive"))
      (node (ref "U2") (pin "1") (pinfunction "COM_1") (pintype "bidirectional"))
    )
    (net (code "70") (name "/bbb5v") (class "Default")
      (node (ref "P9") (pin "7") (pinfunction "7_7") (pintype "passive"))
      (node (ref "P9") (pin "8") (pinfunction "8_8") (pintype "passive"))
      (node (ref "R127") (pin "2") (pinfunction "2_2") (pintype "passive"))
    )
    (net (code "71") (name "/bbb_5v_2a") (class "Default")
      (node (ref "P9") (pin "5") (pinfunction "5_5") (pintype "passive"))
      (node (ref "P9") (pin "6") (pinfunction "6_6") (pintype "passive"))
      (node (ref "R125") (pin "2") (pinfunction "2_2") (pintype "passive"))
    )
    (net (code "72") (name "/p811") (class "Default")
      (node (ref "P8") (pin "11") (pinfunction "11_11") (pintype "passive"))
    )
    (net (code "73") (name "/vref1.8") (class "Default")
      (node (ref "P9") (pin "32") (pinfunction "32_32") (pintype "passive"))
      (node (ref "R130") (pin "1") (pinfunction "1_1") (pintype "passive"))
    )
    (net (code "74") (name "3.3V_PC") (class "Default")
      (node (ref "J4") (pin "3") (pinfunction "3_3") (pintype "passive"))
      (node (ref "U3") (pin "1") (pinfunction "VCC1_1") (pintype "passive"))
      (node (ref "U4") (pin "16") (pinfunction "VCC2_16") (pintype "passive"))
    )
    (net (code "75") (name "3.3vBBB") (class "Default")
      (node (ref "C17") (pin "1") (pinfunction "1_1") (pintype "passive"))
      (node (ref "C18") (pin "1") (pinfunction "1_1") (pintype "passive"))
      (node (ref "C19") (pin "1") (pinfunction "1_1") (pintype "passive"))
      (node (ref "P4") (pin "2") (pinfunction "2_2") (pintype "passive"))
      (node (ref "P9") (pin "3") (pinfunction "3_3") (pintype "passive"))
      (node (ref "P9") (pin "4") (pinfunction "4_4") (pintype "passive"))
      (node (ref "R124") (pin "1") (pinfunction "1_1") (pintype "passive"))
      (node (ref "R124") (pin "2") (pinfunction "2_2") (pintype "passive"))
      (node (ref "R131") (pin "2") (pinfunction "2_2") (pintype "passive"))
      (node (ref "R97") (pin "2") (pinfunction "2_2") (pintype "passive"))
      (node (ref "R98") (pin "2") (pinfunction "2_2") (pintype "passive"))
      (node (ref "U1") (pin "20") (pinfunction "VCC_20") (pintype "power_in"))
      (node (ref "U2") (pin "24") (pinfunction "VCC_24") (pintype "power_in"))
      (node (ref "U3") (pin "16") (pinfunction "VCC2_16") (pintype "passive"))
      (node (ref "U4") (pin "1") (pinfunction "VCC1_1") (pintype "passive"))
    )
    (net (code "76") (name "BBB_GND") (class "Default")
      (node (ref "C1") (pin "2") (pinfunction "2_2") (pintype "passive"))
      (node (ref "C10") (pin "2") (pinfunction "2_2") (pintype "passive"))
      (node (ref "C11") (pin "2") (pinfunction "2_2") (pintype "passive"))
      (node (ref "C12") (pin "2") (pinfunction "2_2") (pintype "passive"))
      (node (ref "C13") (pin "2") (pinfunction "2_2") (pintype "passive"))
      (node (ref "C14") (pin "2") (pinfunction "2_2") (pintype "passive"))
      (node (ref "C15") (pin "2") (pinfunction "2_2") (pintype "passive"))
      (node (ref "C16") (pin "2") (pinfunction "2_2") (pintype "passive"))
      (node (ref "C17") (pin "2") (pinfunction "2_2") (pintype "passive"))
      (node (ref "C18") (pin "2") (pinfunction "2_2") (pintype "passive"))
      (node (ref "C19") (pin "2") (pinfunction "2_2") (pintype "passive"))
      (node (ref "C2") (pin "2") (pinfunction "2_2") (pintype "passive"))
      (node (ref "C20") (pin "2") (pinfunction "2_2") (pintype "passive"))
      (node (ref "C21") (pin "2") (pinfunction "2_2") (pintype "passive"))
      (node (ref "C3") (pin "2") (pinfunction "2_2") (pintype "passive"))
      (node (ref "C4") (pin "2") (pinfunction "2_2") (pintype "passive"))
      (node (ref "C5") (pin "2") (pinfunction "2_2") (pintype "passive"))
      (node (ref "C6") (pin "2") (pinfunction "2_2") (pintype "passive"))
      (node (ref "C7") (pin "2") (pinfunction "2_2") (pintype "passive"))
      (node (ref "C8") (pin "2") (pinfunction "2_2") (pintype "passive"))
      (node (ref "C9") (pin "2") (pinfunction "2_2") (pintype "passive"))
      (node (ref "IC1") (pin "11") (pinfunction "11_11") (pintype "passive"))
      (node (ref "IC2") (pin "11") (pinfunction "11_11") (pintype "passive"))
      (node (ref "IC3") (pin "11") (pinfunction "11_11") (pintype "passive"))
      (node (ref "IC4") (pin "11") (pinfunction "11_11") (pintype "passive"))
      (node (ref "IC5") (pin "11") (pinfunction "11_11") (pintype "passive"))
      (node (ref "IC5") (pin "13") (pinfunction "13_13") (pintype "passive"))
      (node (ref "IC5") (pin "6") (pinfunction "6_6") (pintype "passive"))
      (node (ref "IC5") (pin "9") (pinfunction "9_9") (pintype "passive"))
      (node (ref "LED1") (pin "K") (pinfunction "K_K") (pintype "passive"))
      (node (ref "LED2") (pin "K") (pinfunction "K_K") (pintype "passive"))
      (node (ref "P4") (pin "1") (pinfunction "1_1") (pintype "passive"))
      (node (ref "P8") (pin "1") (pinfunction "1_1") (pintype "passive"))
      (node (ref "P8") (pin "2") (pinfunction "2_2") (pintype "passive"))
      (node (ref "P9") (pin "1") (pinfunction "1_1") (pintype "passive"))
      (node (ref "P9") (pin "2") (pinfunction "2_2") (pintype "passive"))
      (node (ref "R1") (pin "2") (pinfunction "2_2") (pintype "passive"))
      (node (ref "R11") (pin "2") (pinfunction "2_2") (pintype "passive"))
      (node (ref "R12") (pin "2") (pinfunction "2_2") (pintype "passive"))
      (node (ref "R17") (pin "2") (pinfunction "2_2") (pintype "passive"))
      (node (ref "R18") (pin "2") (pinfunction "2_2") (pintype "passive"))
      (node (ref "R22") (pin "2") (pinfunction "2_2") (pintype "passive"))
      (node (ref "R25") (pin "2") (pinfunction "2_2") (pintype "passive"))
      (node (ref "R27") (pin "2") (pinfunction "2_2") (pintype "passive"))
      (node (ref "R33") (pin "2") (pinfunction "2_2") (pintype "passive"))
      (node (ref "R35") (pin "2") (pinfunction "2_2") (pintype "passive"))
      (node (ref "R45") (pin "2") (pinfunction "2_2") (pintype "passive"))
      (node (ref "R46") (pin "2") (pinfunction "2_2") (pintype "passive"))
      (node (ref "R47") (pin "2") (pinfunction "2_2") (pintype "passive"))
      (node (ref "R48") (pin "2") (pinfunction "2_2") (pintype "passive"))
      (node (ref "R49") (pin "2") (pinfunction "2_2") (pintype "passive"))
      (node (ref "R50") (pin "2") (pinfunction "2_2") (pintype "passive"))
      (node (ref "R51") (pin "2") (pinfunction "2_2") (pintype "passive"))
      (node (ref "R52") (pin "2") (pinfunction "2_2") (pintype "passive"))
      (node (ref "R57") (pin "1") (pinfunction "1_1") (pintype "passive"))
      (node (ref "R6") (pin "2") (pinfunction "2_2") (pintype "passive"))
      (node (ref "R62") (pin "1") (pinfunction "1_1") (pintype "passive"))
      (node (ref "R63") (pin "1") (pinfunction "1_1") (pintype "passive"))
      (node (ref "R68") (pin "2") (pinfunction "2_2") (pintype "passive"))
      (node (ref "R69") (pin "1") (pinfunction "1_1") (pintype "passive"))
      (node (ref "R7") (pin "2") (pinfunction "2_2") (pintype "passive"))
      (node (ref "R74") (pin "1") (pinfunction "1_1") (pintype "passive"))
      (node (ref "R75") (pin "1") (pinfunction "1_1") (pintype "passive"))
      (node (ref "R80") (pin "2") (pinfunction "2_2") (pintype "passive"))
      (node (ref "R84") (pin "1") (pinfunction "1_1") (pintype "passive"))
      (node (ref "R85") (pin "1") (pinfunction "1_1") (pintype "passive"))
      (node (ref "R92") (pin "1") (pinfunction "1_1") (pintype "passive"))
      (node (ref "R93") (pin "1") (pinfunction "1_1") (pintype "passive"))
      (node (ref "U1") (pin "1") (pinfunction "~{OE}_1") (pintype "input"))
      (node (ref "U1") (pin "10") (pinfunction "GND_10") (pintype "power_in"))
      (node (ref "U2") (pin "12") (pinfunction "GND_12") (pintype "power_in"))
      (node (ref "U3") (pin "15") (pinfunction "GND2_15") (pintype "passive"))
      (node (ref "U3") (pin "9") (pinfunction "GND2_9") (pintype "passive"))
      (node (ref "U4") (pin "2") (pinfunction "GND1_2") (pintype "passive"))
      (node (ref "U4") (pin "8") (pinfunction "GND1_8") (pintype "passive"))
    )
    (net (code "77") (name "Net-(D03-Pad1)") (class "Default")
      (node (ref "D03") (pin "1") (pinfunction "1_1") (pintype "passive"))
      (node (ref "P4") (pin "3") (pinfunction "3_3") (pintype "passive"))
    )
    (net (code "78") (name "Net-(IC1-Pad2)") (class "Default")
      (node (ref "IC1") (pin "2") (pinfunction "2_2") (pintype "passive"))
      (node (ref "R58") (pin "1") (pinfunction "1_1") (pintype "passive"))
      (node (ref "R59") (pin "2") (pinfunction "2_2") (pintype "passive"))
    )
    (net (code "79") (name "Net-(IC1-Pad3)") (class "Default")
      (node (ref "IC1") (pin "3") (pinfunction "3_3") (pintype "passive"))
      (node (ref "R60") (pin "2") (pinfunction "2_2") (pintype "passive"))
      (node (ref "R61") (pin "2") (pinfunction "2_2") (pintype "passive"))
      (node (ref "R62") (pin "2") (pinfunction "2_2") (pintype "passive"))
    )
    (net (code "80") (name "Net-(IC1-Pad5)") (class "Default")
      (node (ref "IC1") (pin "5") (pinfunction "5_5") (pintype "passive"))
      (node (ref "R63") (pin "2") (pinfunction "2_2") (pintype "passive"))
      (node (ref "R64") (pin "2") (pinfunction "2_2") (pintype "passive"))
      (node (ref "R65") (pin "2") (pinfunction "2_2") (pintype "passive"))
    )
    (net (code "81") (name "Net-(IC1-Pad6)") (class "Default")
      (node (ref "IC1") (pin "6") (pinfunction "6_6") (pintype "passive"))
      (node (ref "R66") (pin "2") (pinfunction "2_2") (pintype "passive"))
      (node (ref "R67") (pin "2") (pinfunction "2_2") (pintype "passive"))
    )
    (net (code "82") (name "Net-(IC1-Pad9)") (class "Default")
      (node (ref "IC1") (pin "9") (pinfunction "9_9") (pintype "passive"))
      (node (ref "R10") (pin "2") (pinfunction "2_2") (pintype "passive"))
      (node (ref "R9") (pin "2") (pinfunction "2_2") (pintype "passive"))
    )
    (net (code "83") (name "Net-(IC1-Pad10)") (class "Default")
      (node (ref "IC1") (pin "10") (pinfunction "10_10") (pintype "passive"))
      (node (ref "R39") (pin "1") (pinfunction "1_1") (pintype "passive"))
      (node (ref "R7") (pin "1") (pinfunction "1_1") (pintype "passive"))
      (node (ref "R8") (pin "1") (pinfunction "1_1") (pintype "passive"))
    )
    (net (code "84") (name "Net-(IC1-Pad12)") (class "Default")
      (node (ref "IC1") (pin "12") (pinfunction "12_12") (pintype "passive"))
      (node (ref "R4") (pin "1") (pinfunction "1_1") (pintype "passive"))
      (node (ref "R5") (pin "1") (pinfunction "1_1") (pintype "passive"))
      (node (ref "R6") (pin "1") (pinfunction "1_1") (pintype "passive"))
    )
    (net (code "85") (name "Net-(IC1-Pad13)") (class "Default")
      (node (ref "IC1") (pin "13") (pinfunction "13_13") (pintype "passive"))
      (node (ref "R2") (pin "2") (pinfunction "2_2") (pintype "passive"))
      (node (ref "R3") (pin "1") (pinfunction "1_1") (pintype "passive"))
    )
    (net (code "86") (name "Net-(IC2-Pad2)") (class "Default")
      (node (ref "IC2") (pin "2") (pinfunction "2_2") (pintype "passive"))
      (node (ref "R70") (pin "1") (pinfunction "1_1") (pintype "passive"))
      (node (ref "R71") (pin "2") (pinfunction "2_2") (pintype "passive"))
    )
    (net (code "87") (name "Net-(IC2-Pad3)") (class "Default")
      (node (ref "IC2") (pin "3") (pinfunction "3_3") (pintype "passive"))
      (node (ref "R72") (pin "2") (pinfunction "2_2") (pintype "passive"))
      (node (ref "R73") (pin "2") (pinfunction "2_2") (pintype "passive"))
      (node (ref "R74") (pin "2") (pinfunction "2_2") (pintype "passive"))
    )
    (net (code "88") (name "Net-(IC2-Pad5)") (class "Default")
      (node (ref "IC2") (pin "5") (pinfunction "5_5") (pintype "passive"))
      (node (ref "R75") (pin "2") (pinfunction "2_2") (pintype "passive"))
      (node (ref "R76") (pin "2") (pinfunction "2_2") (pintype "passive"))
      (node (ref "R77") (pin "2") (pinfunction "2_2") (pintype "passive"))
    )
    (net (code "89") (name "Net-(IC2-Pad6)") (class "Default")
      (node (ref "IC2") (pin "6") (pinfunction "6_6") (pintype "passive"))
      (node (ref "R78") (pin "2") (pinfunction "2_2") (pintype "passive"))
      (node (ref "R79") (pin "2") (pinfunction "2_2") (pintype "passive"))
    )
    (net (code "90") (name "Net-(IC2-Pad9)") (class "Default")
      (node (ref "IC2") (pin "9") (pinfunction "9_9") (pintype "passive"))
      (node (ref "R20") (pin "2") (pinfunction "2_2") (pintype "passive"))
      (node (ref "R21") (pin "2") (pinfunction "2_2") (pintype "passive"))
    )
    (net (code "91") (name "Net-(IC2-Pad10)") (class "Default")
      (node (ref "IC2") (pin "10") (pinfunction "10_10") (pintype "passive"))
      (node (ref "R18") (pin "1") (pinfunction "1_1") (pintype "passive"))
      (node (ref "R19") (pin "1") (pinfunction "1_1") (pintype "passive"))
      (node (ref "R40") (pin "1") (pinfunction "1_1") (pintype "passive"))
    )
    (net (code "92") (name "Net-(IC2-Pad12)") (class "Default")
      (node (ref "IC2") (pin "12") (pinfunction "12_12") (pintype "passive"))
      (node (ref "R15") (pin "1") (pinfunction "1_1") (pintype "passive"))
      (node (ref "R16") (pin "1") (pinfunction "1_1") (pintype "passive"))
      (node (ref "R17") (pin "1") (pinfunction "1_1") (pintype "passive"))
    )
    (net (code "93") (name "Net-(IC2-Pad13)") (class "Default")
      (node (ref "IC2") (pin "13") (pinfunction "13_13") (pintype "passive"))
      (node (ref "R13") (pin "2") (pinfunction "2_2") (pintype "passive"))
      (node (ref "R14") (pin "1") (pinfunction "1_1") (pintype "passive"))
    )
    (net (code "94") (name "Net-(IC3-Pad2)") (class "Default")
      (node (ref "IC3") (pin "2") (pinfunction "2_2") (pintype "passive"))
      (node (ref "R53") (pin "2") (pinfunction "2_2") (pintype "passive"))
      (node (ref "R81") (pin "2") (pinfunction "2_2") (pintype "passive"))
    )
    (net (code "95") (name "Net-(IC3-Pad3)") (class "Default")
      (node (ref "IC3") (pin "3") (pinfunction "3_3") (pintype "passive"))
      (node (ref "R82") (pin "2") (pinfunction "2_2") (pintype "passive"))
      (node (ref "R83") (pin "2") (pinfunction "2_2") (pintype "passive"))
      (node (ref "R84") (pin "2") (pinfunction "2_2") (pintype "passive"))
    )
    (net (code "96") (name "Net-(IC3-Pad5)") (class "Default")
      (node (ref "IC3") (pin "5") (pinfunction "5_5") (pintype "passive"))
      (node (ref "R85") (pin "2") (pinfunction "2_2") (pintype "passive"))
      (node (ref "R86") (pin "2") (pinfunction "2_2") (pintype "passive"))
      (node (ref "R87") (pin "2") (pinfunction "2_2") (pintype "passive"))
    )
    (net (code "97") (name "Net-(IC3-Pad6)") (class "Default")
      (node (ref "IC3") (pin "6") (pinfunction "6_6") (pintype "passive"))
      (node (ref "R54") (pin "1") (pinfunction "1_1") (pintype "passive"))
      (node (ref "R88") (pin "2") (pinfunction "2_2") (pintype "passive"))
    )
    (net (code "98") (name "Net-(IC3-Pad9)") (class "Default")
      (node (ref "IC3") (pin "9") (pinfunction "9_9") (pintype "passive"))
      (node (ref "R30") (pin "2") (pinfunction "2_2") (pintype "passive"))
      (node (ref "R42") (pin "1") (pinfunction "1_1") (pintype "passive"))
    )
    (net (code "99") (name "Net-(IC3-Pad10)") (class "Default")
      (node (ref "IC3") (pin "10") (pinfunction "10_10") (pintype "passive"))
      (node (ref "R27") (pin "1") (pinfunction "1_1") (pintype "passive"))
      (node (ref "R28") (pin "1") (pinfunction "1_1") (pintype "passive"))
      (node (ref "R29") (pin "1") (pinfunction "1_1") (pintype "passive"))
    )
    (net (code "100") (name "Net-(IC3-Pad12)") (class "Default")
      (node (ref "IC3") (pin "12") (pinfunction "12_12") (pintype "passive"))
      (node (ref "R24") (pin "1") (pinfunction "1_1") (pintype "passive"))
      (node (ref "R25") (pin "1") (pinfunction "1_1") (pintype "passive"))
      (node (ref "R26") (pin "1") (pinfunction "1_1") (pintype "passive"))
    )
    (net (code "101") (name "Net-(IC3-Pad13)") (class "Default")
      (node (ref "IC3") (pin "13") (pinfunction "13_13") (pintype "passive"))
      (node (ref "R23") (pin "1") (pinfunction "1_1") (pintype "passive"))
      (node (ref "R41") (pin "2") (pinfunction "2_2") (pintype "passive"))
    )
    (net (code "102") (name "Net-(IC4-Pad2)") (class "Default")
      (node (ref "IC4") (pin "2") (pinfunction "2_2") (pintype "passive"))
      (node (ref "R55") (pin "2") (pinfunction "2_2") (pintype "passive"))
      (node (ref "R89") (pin "2") (pinfunction "2_2") (pintype "passive"))
    )
    (net (code "103") (name "Net-(IC4-Pad3)") (class "Default")
      (node (ref "IC4") (pin "3") (pinfunction "3_3") (pintype "passive"))
      (node (ref "R90") (pin "2") (pinfunction "2_2") (pintype "passive"))
      (node (ref "R91") (pin "2") (pinfunction "2_2") (pintype "passive"))
      (node (ref "R92") (pin "2") (pinfunction "2_2") (pintype "passive"))
    )
    (net (code "104") (name "Net-(IC4-Pad5)") (class "Default")
      (node (ref "IC4") (pin "5") (pinfunction "5_5") (pintype "passive"))
      (node (ref "R93") (pin "2") (pinfunction "2_2") (pintype "passive"))
      (node (ref "R94") (pin "2") (pinfunction "2_2") (pintype "passive"))
      (node (ref "R95") (pin "2") (pinfunction "2_2") (pintype "passive"))
    )
    (net (code "105") (name "Net-(IC4-Pad6)") (class "Default")
      (node (ref "IC4") (pin "6") (pinfunction "6_6") (pintype "passive"))
      (node (ref "R56") (pin "1") (pinfunction "1_1") (pintype "passive"))
      (node (ref "R96") (pin "2") (pinfunction "2_2") (pintype "passive"))
    )
    (net (code "106") (name "Net-(IC4-Pad9)") (class "Default")
      (node (ref "IC4") (pin "9") (pinfunction "9_9") (pintype "passive"))
      (node (ref "R38") (pin "2") (pinfunction "2_2") (pintype "passive"))
      (node (ref "R44") (pin "1") (pinfunction "1_1") (pintype "passive"))
    )
    (net (code "107") (name "Net-(IC4-Pad10)") (class "Default")
      (node (ref "IC4") (pin "10") (pinfunction "10_10") (pintype "passive"))
      (node (ref "R35") (pin "1") (pinfunction "1_1") (pintype "passive"))
      (node (ref "R36") (pin "1") (pinfunction "1_1") (pintype "passive"))
      (node (ref "R37") (pin "1") (pinfunction "1_1") (pintype "passive"))
    )
    (net (code "108") (name "Net-(IC4-Pad12)") (class "Default")
      (node (ref "IC4") (pin "12") (pinfunction "12_12") (pintype "passive"))
      (node (ref "R32") (pin "1") (pinfunction "1_1") (pintype "passive"))
      (node (ref "R33") (pin "1") (pinfunction "1_1") (pintype "passive"))
      (node (ref "R34") (pin "1") (pinfunction "1_1") (pintype "passive"))
    )
    (net (code "109") (name "Net-(IC4-Pad13)") (class "Default")
      (node (ref "IC4") (pin "13") (pinfunction "13_13") (pintype "passive"))
      (node (ref "R31") (pin "1") (pinfunction "1_1") (pintype "passive"))
      (node (ref "R43") (pin "2") (pinfunction "2_2") (pintype "passive"))
    )
    (net (code "110") (name "Net-(IC5-Pad3)") (class "Default")
      (node (ref "IC5") (pin "3") (pinfunction "3_3") (pintype "passive"))
      (node (ref "R130") (pin "2") (pinfunction "2_2") (pintype "passive"))
    )
    (net (code "111") (name "Net-(LED1-PadA)") (class "Default")
      (node (ref "LED1") (pin "A") (pinfunction "A_A") (pintype "passive"))
      (node (ref "R131") (pin "1") (pinfunction "1_1") (pintype "passive"))
    )
    (net (code "112") (name "Net-(LED2-PadA)") (class "Default")
      (node (ref "LED2") (pin "A") (pinfunction "A_A") (pintype "passive"))
      (node (ref "R132") (pin "1") (pinfunction "1_1") (pintype "passive"))
    )
    (net (code "113") (name "Net-(U3-INA)") (class "Default")
      (node (ref "J4") (pin "4") (pinfunction "4_4") (pintype "passive"))
      (node (ref "U3") (pin "3") (pinfunction "INA_3") (pintype "passive"))
    )
    (net (code "114") (name "Net-(U3-OUTA)") (class "Default")
      (node (ref "R133") (pin "1") (pinfunction "1_1") (pintype "passive"))
      (node (ref "U3") (pin "14") (pinfunction "OUTA_14") (pintype "passive"))
    )
    (net (code "115") (name "Net-(U4-IND)") (class "Default")
      (node (ref "R134") (pin "1") (pinfunction "1_1") (pintype "passive"))
      (node (ref "U4") (pin "6") (pinfunction "IND_6") (pintype "passive"))
    )
    (net (code "116") (name "Net-(U4-OUTD)") (class "Default")
      (node (ref "J4") (pin "5") (pinfunction "5_5") (pintype "passive"))
      (node (ref "U4") (pin "11") (pinfunction "OUTD_11") (pintype "passive"))
    )
    (net (code "117") (name "PC_GND") (class "Default")
      (node (ref "J4") (pin "1") (pinfunction "1_1") (pintype "passive"))
      (node (ref "U3") (pin "2") (pinfunction "GND1_2") (pintype "passive"))
      (node (ref "U3") (pin "8") (pinfunction "GND1_8") (pintype "passive"))
      (node (ref "U4") (pin "15") (pinfunction "GND2_15") (pintype "passive"))
      (node (ref "U4") (pin "9") (pinfunction "GND2_9") (pintype "passive"))
    )
    (net (code "118") (name "bbb_5V") (class "Default")
      (node (ref "C20") (pin "1") (pinfunction "1_1") (pintype "passive"))
      (node (ref "C21") (pin "1") (pinfunction "1_1") (pintype "passive"))
      (node (ref "D03") (pin "2") (pinfunction "2_2") (pintype "passive"))
      (node (ref "IC5") (pin "10") (pinfunction "10_10") (pintype "passive"))
      (node (ref "IC5") (pin "12") (pinfunction "12_12") (pintype "passive"))
      (node (ref "IC5") (pin "4") (pinfunction "4_4") (pintype "passive"))
      (node (ref "IC5") (pin "5") (pinfunction "5_5") (pintype "passive"))
      (node (ref "R125") (pin "1") (pinfunction "1_1") (pintype "passive"))
      (node (ref "R127") (pin "1") (pinfunction "1_1") (pintype "passive"))
      (node (ref "R132") (pin "2") (pinfunction "2_2") (pintype "passive"))
    )
    (net (code "119") (name "unconnected-(IC5-Pad7)") (class "Default")
      (node (ref "IC5") (pin "7") (pinfunction "7_7") (pintype "passive"))
    )
    (net (code "120") (name "unconnected-(IC5-Pad8)") (class "Default")
      (node (ref "IC5") (pin "8") (pinfunction "8_8") (pintype "passive"))
    )
    (net (code "121") (name "unconnected-(IC5-Pad14)") (class "Default")
      (node (ref "IC5") (pin "14") (pinfunction "14_14") (pintype "passive"))
    )
    (net (code "122") (name "unconnected-(J1-Pad2)") (class "Default")
      (node (ref "J1") (pin "2") (pinfunction "2_2") (pintype "passive"))
    )
    (net (code "123") (name "unconnected-(J1-Pad3)") (class "Default")
      (node (ref "J1") (pin "3") (pinfunction "3_3") (pintype "passive"))
    )
    (net (code "124") (name "unconnected-(J1-Pad6)") (class "Default")
      (node (ref "J1") (pin "6") (pinfunction "6_6") (pintype "passive"))
    )
    (net (code "125") (name "unconnected-(J4-Pad2)") (class "Default")
      (node (ref "J4") (pin "2") (pinfunction "2_2") (pintype "passive"))
    )
    (net (code "126") (name "unconnected-(J4-Pad6)") (class "Default")
      (node (ref "J4") (pin "6") (pinfunction "6_6") (pintype "passive"))
    )
    (net (code "127") (name "unconnected-(P8-Pad3)") (class "Default")
      (node (ref "P8") (pin "3") (pinfunction "3_3") (pintype "passive"))
    )
    (net (code "128") (name "unconnected-(P8-Pad4)") (class "Default")
      (node (ref "P8") (pin "4") (pinfunction "4_4") (pintype "passive"))
    )
    (net (code "129") (name "unconnected-(P8-Pad5)") (class "Default")
      (node (ref "P8") (pin "5") (pinfunction "5_5") (pintype "passive"))
    )
    (net (code "130") (name "unconnected-(P8-Pad6)") (class "Default")
      (node (ref "P8") (pin "6") (pinfunction "6_6") (pintype "passive"))
    )
    (net (code "131") (name "unconnected-(P8-Pad13)") (class "Default")
      (node (ref "P8") (pin "13") (pinfunction "13_13") (pintype "passive"))
    )
    (net (code "132") (name "unconnected-(P8-Pad15)") (class "Default")
      (node (ref "P8") (pin "15") (pinfunction "15_15") (pintype "passive"))
    )
    (net (code "133") (name "unconnected-(P8-Pad17)") (class "Default")
      (node (ref "P8") (pin "17") (pinfunction "17_17") (pintype "passive"))
    )
    (net (code "134") (name "unconnected-(P8-Pad19)") (class "Default")
      (node (ref "P8") (pin "19") (pinfunction "19_19") (pintype "passive"))
    )
    (net (code "135") (name "unconnected-(P8-Pad20)") (class "Default")
      (node (ref "P8") (pin "20") (pinfunction "20_20") (pintype "passive"))
    )
    (net (code "136") (name "unconnected-(P8-Pad21)") (class "Default")
      (node (ref "P8") (pin "21") (pinfunction "21_21") (pintype "passive"))
    )
    (net (code "137") (name "unconnected-(P8-Pad22)") (class "Default")
      (node (ref "P8") (pin "22") (pinfunction "22_22") (pintype "passive"))
    )
    (net (code "138") (name "unconnected-(P8-Pad23)") (class "Default")
      (node (ref "P8") (pin "23") (pinfunction "23_23") (pintype "passive"))
    )
    (net (code "139") (name "unconnected-(P8-Pad24)") (class "Default")
      (node (ref "P8") (pin "24") (pinfunction "24_24") (pintype "passive"))
    )
    (net (code "140") (name "unconnected-(P8-Pad25)") (class "Default")
      (node (ref "P8") (pin "25") (pinfunction "25_25") (pintype "passive"))
    )
    (net (code "141") (name "unconnected-(P8-Pad26)") (class "Default")
      (node (ref "P8") (pin "26") (pinfunction "26_26") (pintype "passive"))
    )
    (net (code "142") (name "unconnected-(P8-Pad27)") (class "Default")
      (node (ref "P8") (pin "27") (pinfunction "27_27") (pintype "passive"))
    )
    (net (code "143") (name "unconnected-(P8-Pad28)") (class "Default")
      (node (ref "P8") (pin "28") (pinfunction "28_28") (pintype "passive"))
    )
    (net (code "144") (name "unconnected-(P8-Pad29)") (class "Default")
      (node (ref "P8") (pin "29") (pinfunction "29_29") (pintype "passive"))
    )
    (net (code "145") (name "unconnected-(P8-Pad30)") (class "Default")
      (node (ref "P8") (pin "30") (pinfunction "30_30") (pintype "passive"))
    )
    (net (code "146") (name "unconnected-(P8-Pad31)") (class "Default")
      (node (ref "P8") (pin "31") (pinfunction "31_31") (pintype "passive"))
    )
    (net (code "147") (name "unconnected-(P8-Pad32)") (class "Default")
      (node (ref "P8") (pin "32") (pinfunction "32_32") (pintype "passive"))
    )
    (net (code "148") (name "unconnected-(P8-Pad33)") (class "Default")
      (node (ref "P8") (pin "33") (pinfunction "33_33") (pintype "passive"))
    )
    (net (code "149") (name "unconnected-(P8-Pad34)") (class "Default")
      (node (ref "P8") (pin "34") (pinfunction "34_34") (pintype "passive"))
    )
    (net (code "150") (name "unconnected-(P8-Pad35)") (class "Default")
      (node (ref "P8") (pin "35") (pinfunction "35_35") (pintype "passive"))
    )
    (net (code "151") (name "unconnected-(P8-Pad36)") (class "Default")
      (node (ref "P8") (pin "36") (pinfunction "36_36") (pintype "passive"))
    )
    (net (code "152") (name "unconnected-(P8-Pad37)") (class "Default")
      (node (ref "P8") (pin "37") (pinfunction "37_37") (pintype "passive"))
    )
    (net (code "153") (name "unconnected-(P8-Pad38)") (class "Default")
      (node (ref "P8") (pin "38") (pinfunction "38_38") (pintype "passive"))
    )
    (net (code "154") (name "unconnected-(P8-Pad39)") (class "Default")
      (node (ref "P8") (pin "39") (pinfunction "39_39") (pintype "passive"))
    )
    (net (code "155") (name "unconnected-(P8-Pad40)") (class "Default")
      (node (ref "P8") (pin "40") (pinfunction "40_40") (pintype "passive"))
    )
    (net (code "156") (name "unconnected-(P8-Pad41)") (class "Default")
      (node (ref "P8") (pin "41") (pinfunction "41_41") (pintype "passive"))
    )
    (net (code "157") (name "unconnected-(P8-Pad42)") (class "Default")
      (node (ref "P8") (pin "42") (pinfunction "42_42") (pintype "passive"))
    )
    (net (code "158") (name "unconnected-(P8-Pad43)") (class "Default")
      (node (ref "P8") (pin "43") (pinfunction "43_43") (pintype "passive"))
    )
    (net (code "159") (name "unconnected-(P8-Pad44)") (class "Default")
      (node (ref "P8") (pin "44") (pinfunction "44_44") (pintype "passive"))
    )
    (net (code "160") (name "unconnected-(P8-Pad45)") (class "Default")
      (node (ref "P8") (pin "45") (pinfunction "45_45") (pintype "passive"))
    )
    (net (code "161") (name "unconnected-(P8-Pad46)") (class "Default")
      (node (ref "P8") (pin "46") (pinfunction "46_46") (pintype "passive"))
    )
    (net (code "162") (name "unconnected-(P8-Pad47)") (class "Default")
      (node (ref "P8") (pin "47") (pinfunction "47_47") (pintype "passive"))
    )
    (net (code "163") (name "unconnected-(P8-Pad48)") (class "Default")
      (node (ref "P8") (pin "48") (pinfunction "48_48") (pintype "passive"))
    )
    (net (code "164") (name "unconnected-(P8-Pad49)") (class "Default")
      (node (ref "P8") (pin "49") (pinfunction "49_49") (pintype "passive"))
    )
    (net (code "165") (name "unconnected-(P8-Pad50)") (class "Default")
      (node (ref "P8") (pin "50") (pinfunction "50_50") (pintype "passive"))
    )
    (net (code "166") (name "unconnected-(P9-Pad9)") (class "Default")
      (node (ref "P9") (pin "9") (pinfunction "9_9") (pintype "passive"))
    )
    (net (code "167") (name "unconnected-(P9-Pad10)") (class "Default")
      (node (ref "P9") (pin "10") (pinfunction "10_10") (pintype "passive"))
    )
    (net (code "168") (name "unconnected-(P9-Pad18)") (class "Default")
      (node (ref "P9") (pin "18") (pinfunction "18_18") (pintype "passive"))
    )
    (net (code "169") (name "unconnected-(P9-Pad19)") (class "Default")
      (node (ref "P9") (pin "19") (pinfunction "19_19") (pintype "passive"))
    )
    (net (code "170") (name "unconnected-(P9-Pad20)") (class "Default")
      (node (ref "P9") (pin "20") (pinfunction "20_20") (pintype "passive"))
    )
    (net (code "171") (name "unconnected-(P9-Pad21)") (class "Default")
      (node (ref "P9") (pin "21") (pinfunction "21_21") (pintype "passive"))
    )
    (net (code "172") (name "unconnected-(P9-Pad22)") (class "Default")
      (node (ref "P9") (pin "22") (pinfunction "22_22") (pintype "passive"))
    )
    (net (code "173") (name "unconnected-(P9-Pad23)") (class "Default")
      (node (ref "P9") (pin "23") (pinfunction "23_23") (pintype "passive"))
    )
    (net (code "174") (name "unconnected-(P9-Pad25)") (class "Default")
      (node (ref "P9") (pin "25") (pinfunction "25_25") (pintype "passive"))
    )
    (net (code "175") (name "unconnected-(P9-Pad26)") (class "Default")
      (node (ref "P9") (pin "26") (pinfunction "26_26") (pintype "passive"))
    )
    (net (code "176") (name "unconnected-(P9-Pad27)") (class "Default")
      (node (ref "P9") (pin "27") (pinfunction "27_27") (pintype "passive"))
    )
    (net (code "177") (name "unconnected-(P9-Pad28)") (class "Default")
      (node (ref "P9") (pin "28") (pinfunction "28_28") (pintype "passive"))
    )
    (net (code "178") (name "unconnected-(P9-Pad29)") (class "Default")
      (node (ref "P9") (pin "29") (pinfunction "29_29") (pintype "passive"))
    )
    (net (code "179") (name "unconnected-(P9-Pad30)") (class "Default")
      (node (ref "P9") (pin "30") (pinfunction "30_30") (pintype "passive"))
    )
    (net (code "180") (name "unconnected-(P9-Pad31)") (class "Default")
      (node (ref "P9") (pin "31") (pinfunction "31_31") (pintype "passive"))
    )
    (net (code "181") (name "unconnected-(P9-Pad34)") (class "Default")
      (node (ref "P9") (pin "34") (pinfunction "34_34") (pintype "passive"))
    )
    (net (code "182") (name "unconnected-(P9-Pad41)") (class "Default")
      (node (ref "P9") (pin "41") (pinfunction "41_41") (pintype "passive"))
    )
    (net (code "183") (name "unconnected-(P9-Pad42)") (class "Default")
      (node (ref "P9") (pin "42") (pinfunction "42_42") (pintype "passive"))
    )
    (net (code "184") (name "unconnected-(P9-Pad43)") (class "Default")
      (node (ref "P9") (pin "43") (pinfunction "43_43") (pintype "passive"))
    )
    (net (code "185") (name "unconnected-(P9-Pad44)") (class "Default")
      (node (ref "P9") (pin "44") (pinfunction "44_44") (pintype "passive"))
    )
    (net (code "186") (name "unconnected-(P9-Pad45)") (class "Default")
      (node (ref "P9") (pin "45") (pinfunction "45_45") (pintype "passive"))
    )
    (net (code "187") (name "unconnected-(P9-Pad46)") (class "Default")
      (node (ref "P9") (pin "46") (pinfunction "46_46") (pintype "passive"))
    )
    (net (code "188") (name "unconnected-(P9-Pad47)") (class "Default")
      (node (ref "P9") (pin "47") (pinfunction "47_47") (pintype "passive"))
    )
    (net (code "189") (name "unconnected-(P9-Pad48)") (class "Default")
      (node (ref "P9") (pin "48") (pinfunction "48_48") (pintype "passive"))
    )
    (net (code "190") (name "unconnected-(P9-Pad49)") (class "Default")
      (node (ref "P9") (pin "49") (pinfunction "49_49") (pintype "passive"))
    )
    (net (code "191") (name "unconnected-(P9-Pad50)") (class "Default")
      (node (ref "P9") (pin "50") (pinfunction "50_50") (pintype "passive"))
    )
    (net (code "192") (name "unconnected-(R109-Pad1)") (class "Default")
      (node (ref "R109") (pin "1") (pinfunction "1_1") (pintype "passive"))
    )
    (net (code "193") (name "unconnected-(R112-Pad1)") (class "Default")
      (node (ref "R112") (pin "1") (pinfunction "1_1") (pintype "passive"))
    )
    (net (code "194") (name "unconnected-(R118-Pad1)") (class "Default")
      (node (ref "R118") (pin "1") (pinfunction "1_1") (pintype "passive"))
    )
    (net (code "195") (name "unconnected-(U1-D5-Pad6)") (class "Default")
      (node (ref "U1") (pin "6") (pinfunction "D5_6") (pintype "input+no_connect"))
    )
    (net (code "196") (name "unconnected-(U1-D6-Pad7)") (class "Default")
      (node (ref "U1") (pin "7") (pinfunction "D6_7") (pintype "input+no_connect"))
    )
    (net (code "197") (name "unconnected-(U1-D7-Pad8)") (class "Default")
      (node (ref "U1") (pin "8") (pinfunction "D7_8") (pintype "input+no_connect"))
    )
    (net (code "198") (name "unconnected-(U1-D8-Pad9)") (class "Default")
      (node (ref "U1") (pin "9") (pinfunction "D8_9") (pintype "input+no_connect"))
    )
    (net (code "199") (name "unconnected-(U1-Q5-Pad15)") (class "Default")
      (node (ref "U1") (pin "15") (pinfunction "Q5_15") (pintype "tri_state"))
    )
    (net (code "200") (name "unconnected-(U1-Q6-Pad14)") (class "Default")
      (node (ref "U1") (pin "14") (pinfunction "Q6_14") (pintype "tri_state"))
    )
    (net (code "201") (name "unconnected-(U1-Q7-Pad13)") (class "Default")
      (node (ref "U1") (pin "13") (pinfunction "Q7_13") (pintype "tri_state"))
    )
    (net (code "202") (name "unconnected-(U1-Q8-Pad12)") (class "Default")
      (node (ref "U1") (pin "12") (pinfunction "Q8_12") (pintype "tri_state"))
    )
    (net (code "203") (name "unconnected-(U3-EN-Pad10)") (class "Default")
      (node (ref "U3") (pin "10") (pinfunction "EN_10") (pintype "passive"))
    )
    (net (code "204") (name "unconnected-(U3-INB-Pad4)") (class "Default")
      (node (ref "U3") (pin "4") (pinfunction "INB_4") (pintype "passive"))
    )
    (net (code "205") (name "unconnected-(U3-INC-Pad5)") (class "Default")
      (node (ref "U3") (pin "5") (pinfunction "INC_5") (pintype "passive"))
    )
    (net (code "206") (name "unconnected-(U3-IND-Pad6)") (class "Default")
      (node (ref "U3") (pin "6") (pinfunction "IND_6") (pintype "passive"))
    )
    (net (code "207") (name "unconnected-(U3-NC-Pad7)") (class "Default")
      (node (ref "U3") (pin "7") (pinfunction "NC_7") (pintype "passive"))
    )
    (net (code "208") (name "unconnected-(U3-OUTB-Pad13)") (class "Default")
      (node (ref "U3") (pin "13") (pinfunction "OUTB_13") (pintype "passive"))
    )
    (net (code "209") (name "unconnected-(U3-OUTC-Pad12)") (class "Default")
      (node (ref "U3") (pin "12") (pinfunction "OUTC_12") (pintype "passive"))
    )
    (net (code "210") (name "unconnected-(U3-OUTD-Pad11)") (class "Default")
      (node (ref "U3") (pin "11") (pinfunction "OUTD_11") (pintype "passive"))
    )
    (net (code "211") (name "unconnected-(U4-EN-Pad10)") (class "Default")
      (node (ref "U4") (pin "10") (pinfunction "EN_10") (pintype "passive"))
    )
    (net (code "212") (name "unconnected-(U4-INA-Pad3)") (class "Default")
      (node (ref "U4") (pin "3") (pinfunction "INA_3") (pintype "passive"))
    )
    (net (code "213") (name "unconnected-(U4-INB-Pad4)") (class "Default")
      (node (ref "U4") (pin "4") (pinfunction "INB_4") (pintype "passive"))
    )
    (net (code "214") (name "unconnected-(U4-INC-Pad5)") (class "Default")
      (node (ref "U4") (pin "5") (pinfunction "INC_5") (pintype "passive"))
    )
    (net (code "215") (name "unconnected-(U4-NC-Pad7)") (class "Default")
      (node (ref "U4") (pin "7") (pinfunction "NC_7") (pintype "passive"))
    )
    (net (code "216") (name "unconnected-(U4-OUTA-Pad14)") (class "Default")
      (node (ref "U4") (pin "14") (pinfunction "OUTA_14") (pintype "passive"))
    )
    (net (code "217") (name "unconnected-(U4-OUTB-Pad13)") (class "Default")
      (node (ref "U4") (pin "13") (pinfunction "OUTB_13") (pintype "passive"))
    )
    (net (code "218") (name "unconnected-(U4-OUTC-Pad12)") (class "Default")
      (node (ref "U4") (pin "12") (pinfunction "OUTC_12") (pintype "passive"))
    )
  )
)
